# ADC2.net
KiCad netlist of a schematic drawn in EAGLE
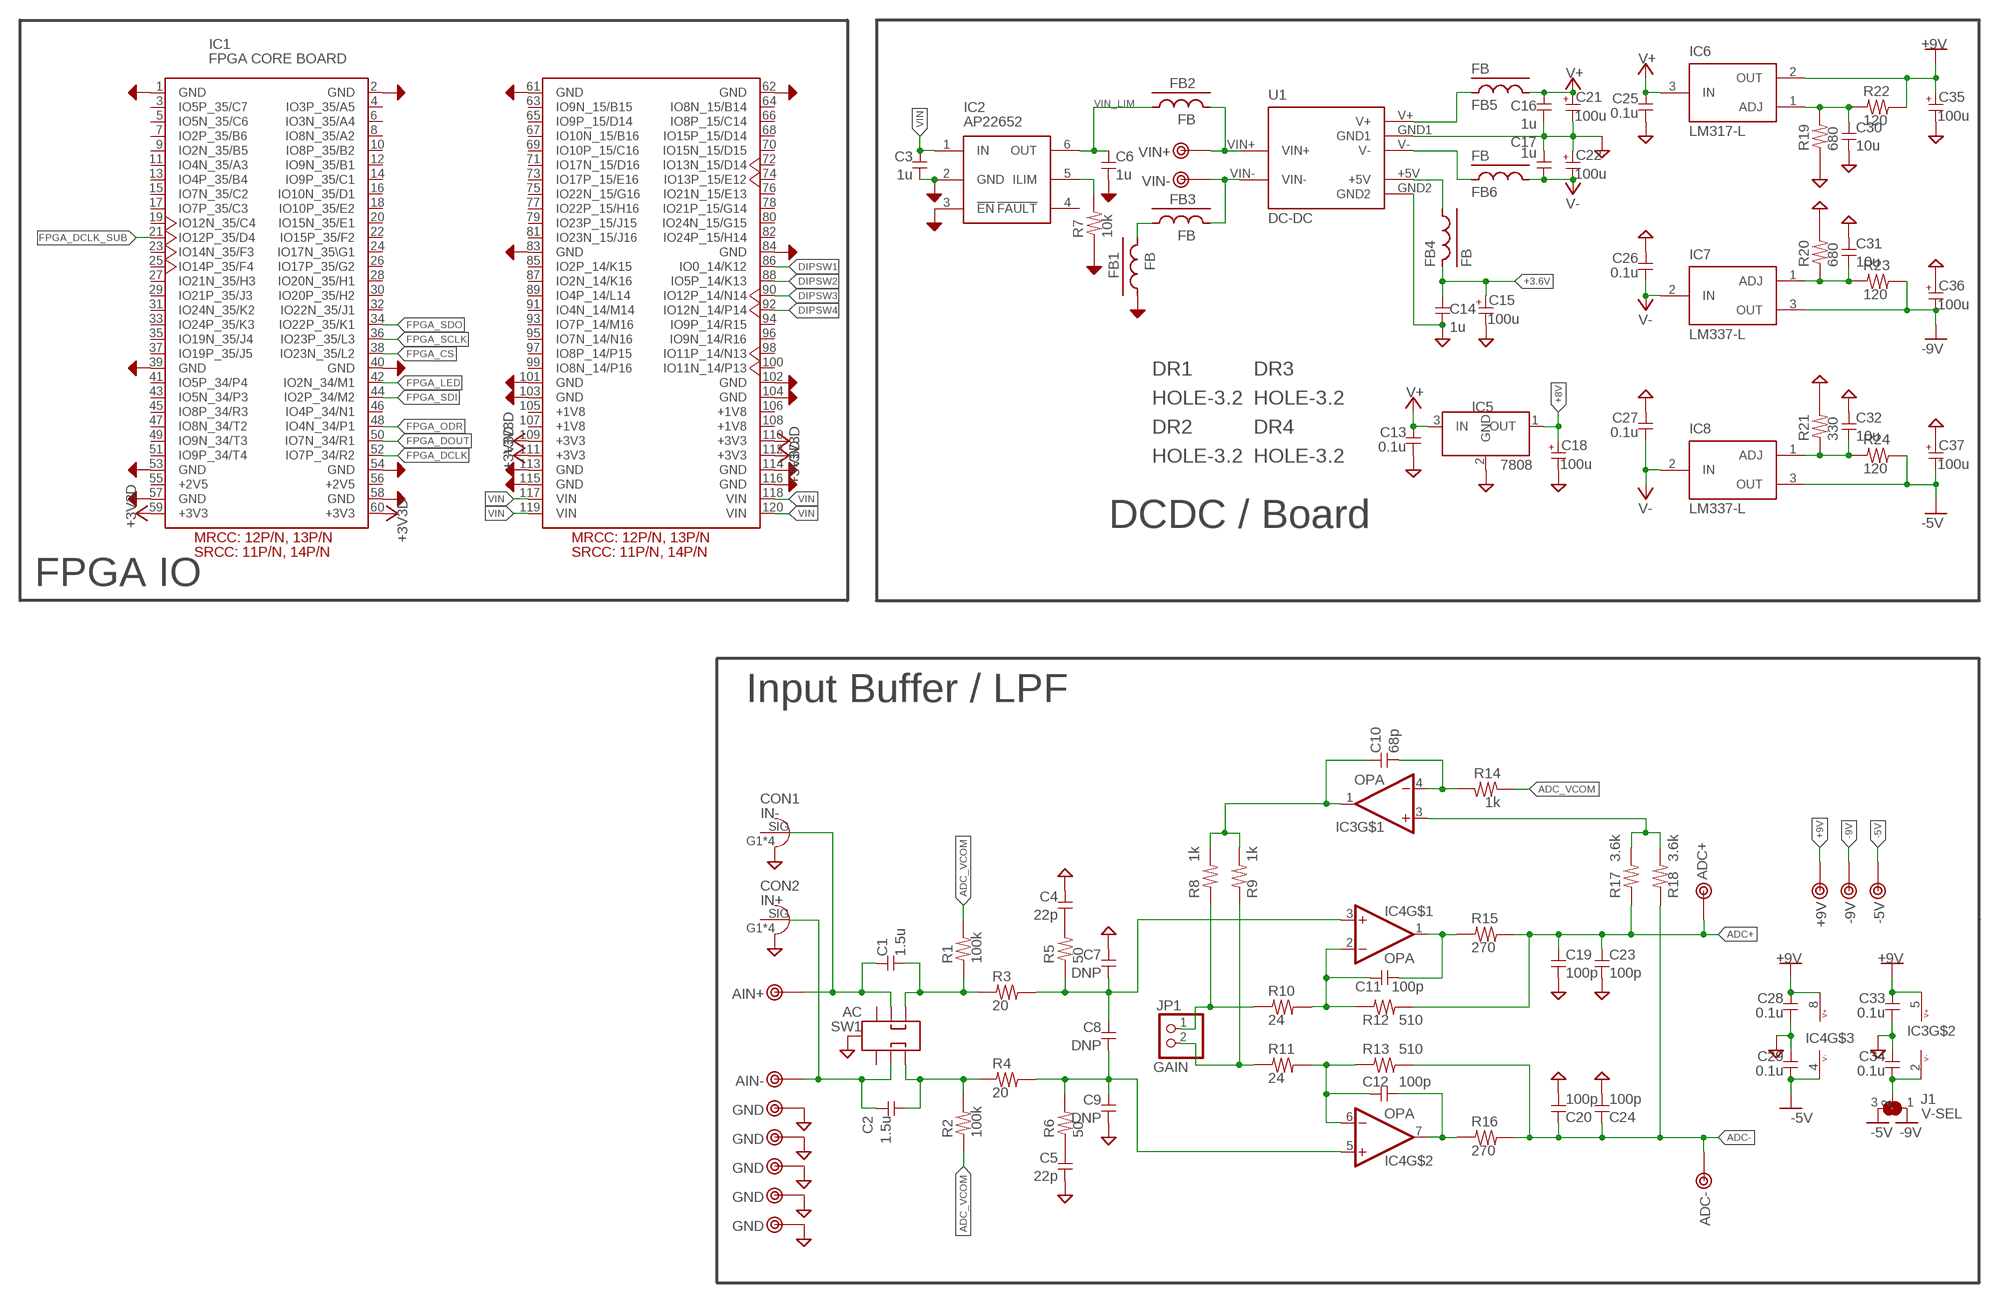
[diagram p0: schematic, sheet 1, part 1 of 2]
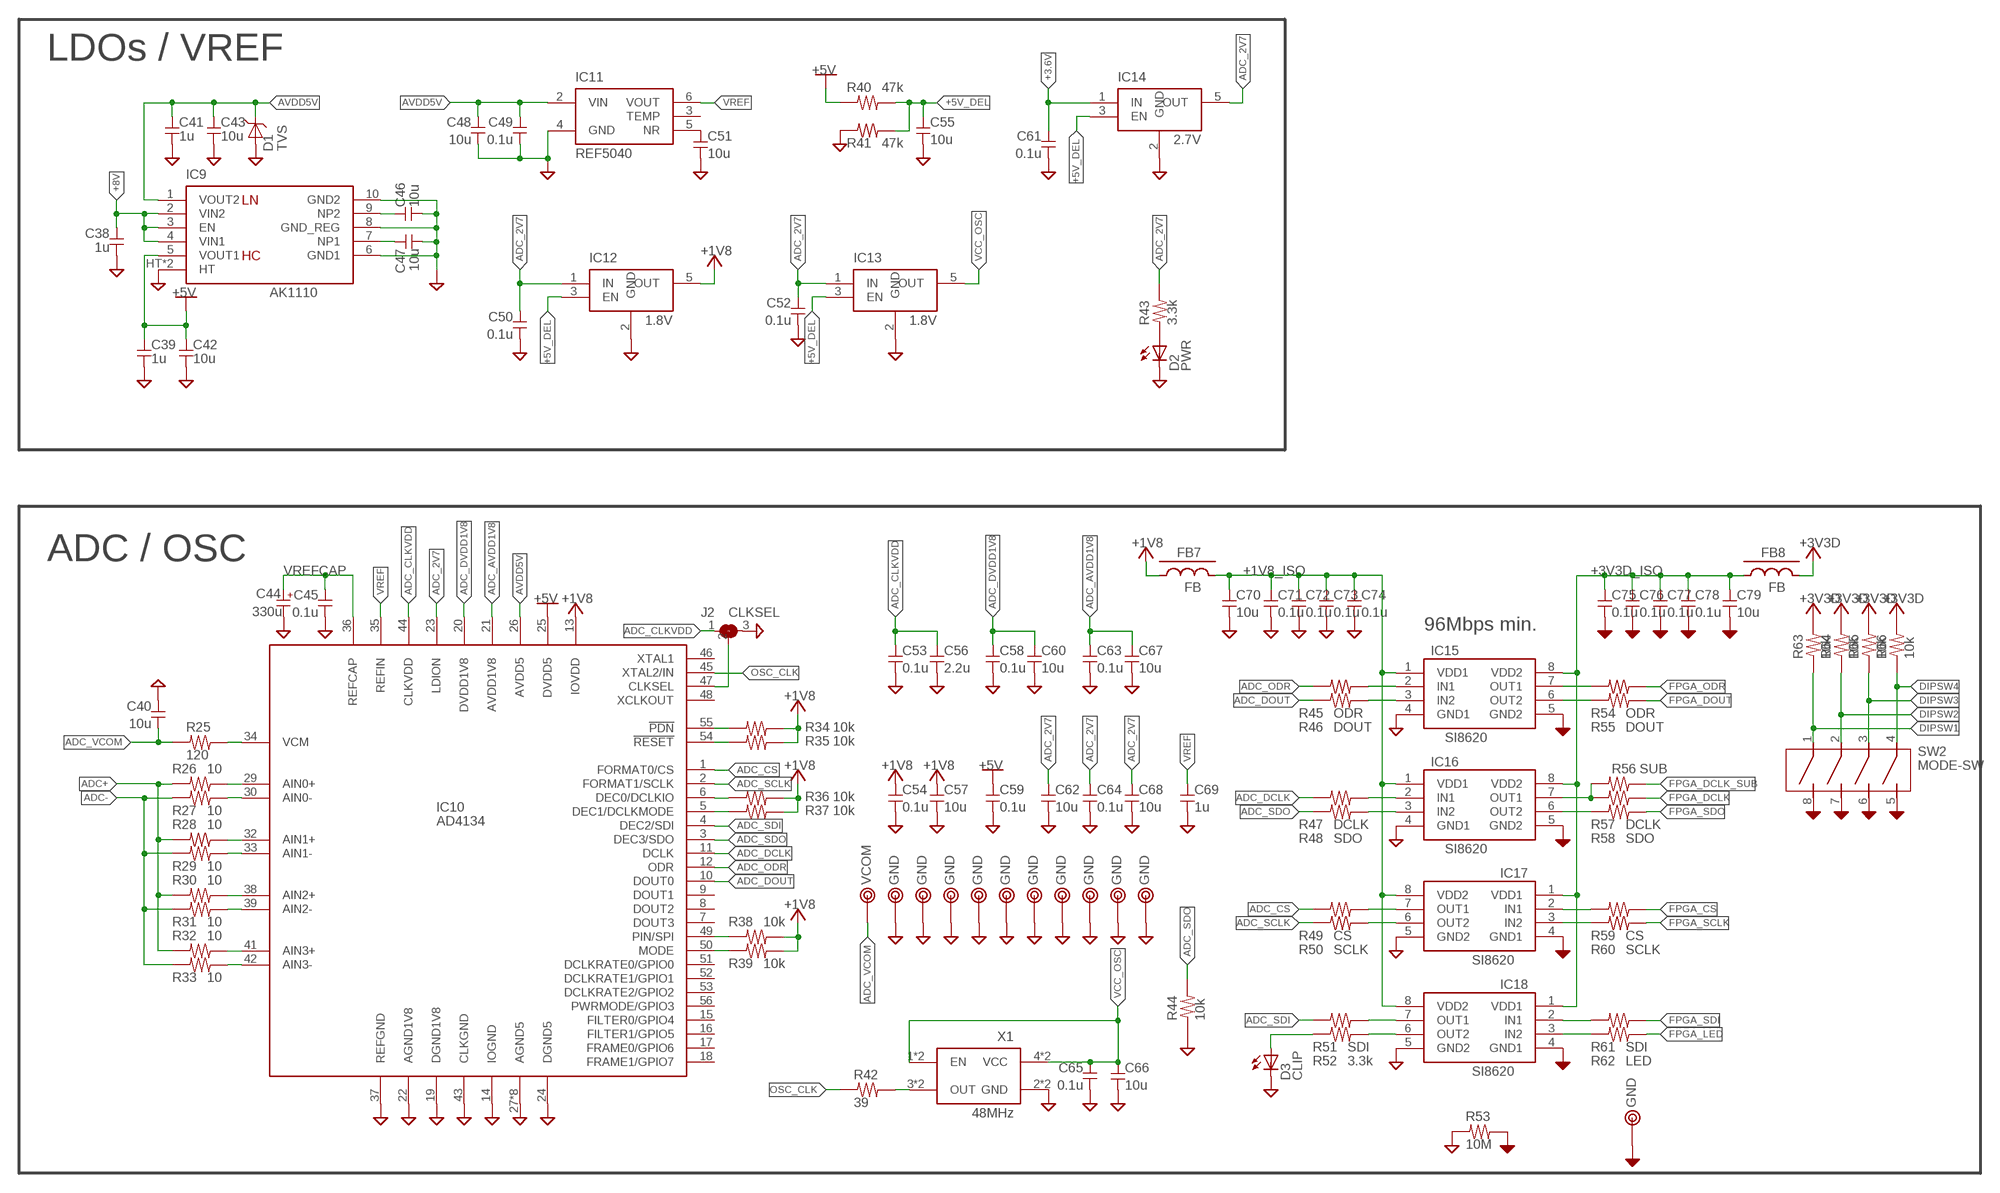
[diagram p1: schematic, sheet 1, part 2 of 2]

(export (version "E")
  (design (tool "Eeschema 10.0.6"))
  (components
    (comp (ref "C1")
      (value "1.5u")
      (footprint "eagle-import:C050")
      (libsource (lib "eagle-import") (part "C-5"))
    )
    (comp (ref "C2")
      (value "1.5u")
      (footprint "eagle-import:C050")
      (libsource (lib "eagle-import") (part "C-5"))
    )
    (comp (ref "C3")
      (value "1u")
      (footprint "eagle-import:1608C")
      (libsource (lib "eagle-import") (part "C-1608"))
    )
    (comp (ref "C4")
      (value "22p")
      (footprint "eagle-import:1608C")
      (libsource (lib "eagle-import") (part "C-1608"))
    )
    (comp (ref "C5")
      (value "22p")
      (footprint "eagle-import:1608C")
      (libsource (lib "eagle-import") (part "C-1608"))
    )
    (comp (ref "C6")
      (value "1u")
      (footprint "eagle-import:1608C")
      (libsource (lib "eagle-import") (part "C-1608"))
    )
    (comp (ref "C7")
      (value "DNP")
      (footprint "eagle-import:1608C")
      (libsource (lib "eagle-import") (part "C-1608"))
    )
    (comp (ref "C8")
      (value "DNP")
      (footprint "eagle-import:1608-3")
      (libsource (lib "eagle-import") (part "C-1608-3"))
    )
    (comp (ref "C9")
      (value "DNP")
      (footprint "eagle-import:1608C")
      (libsource (lib "eagle-import") (part "C-1608"))
    )
    (comp (ref "C10")
      (value "68p")
      (footprint "eagle-import:1608-3")
      (libsource (lib "eagle-import") (part "C-1608-3"))
    )
    (comp (ref "C11")
      (value "100p")
      (footprint "eagle-import:1608C")
      (libsource (lib "eagle-import") (part "C-1608"))
    )
    (comp (ref "C12")
      (value "100p")
      (footprint "eagle-import:1608C")
      (libsource (lib "eagle-import") (part "C-1608"))
    )
    (comp (ref "C13")
      (value "0.1u")
      (footprint "eagle-import:1608C")
      (libsource (lib "eagle-import") (part "C-1608"))
    )
    (comp (ref "C14")
      (value "1u")
      (footprint "eagle-import:1608C")
      (libsource (lib "eagle-import") (part "C-1608"))
    )
    (comp (ref "C15")
      (value "100u")
      (footprint "eagle-import:E2,5-8")
      (libsource (lib "eagle-import") (part "CPOLE2.5-8"))
    )
    (comp (ref "C16")
      (value "1u")
      (footprint "eagle-import:1608C")
      (libsource (lib "eagle-import") (part "C-1608"))
    )
    (comp (ref "C17")
      (value "1u")
      (footprint "eagle-import:1608C")
      (libsource (lib "eagle-import") (part "C-1608"))
    )
    (comp (ref "C18")
      (value "100u")
      (footprint "eagle-import:E2.5-6.5")
      (libsource (lib "eagle-import") (part "CPOLE2.5-6.5"))
    )
    (comp (ref "C19")
      (value "100p")
      (footprint "eagle-import:1608-3")
      (libsource (lib "eagle-import") (part "C-1608-3"))
    )
    (comp (ref "C20")
      (value "100p")
      (footprint "eagle-import:1608-3")
      (libsource (lib "eagle-import") (part "C-1608-3"))
    )
    (comp (ref "C21")
      (value "100u")
      (footprint "eagle-import:E2,5-8")
      (libsource (lib "eagle-import") (part "CPOLE2.5-8"))
    )
    (comp (ref "C22")
      (value "100u")
      (footprint "eagle-import:E2,5-8")
      (libsource (lib "eagle-import") (part "CPOLE2.5-8"))
    )
    (comp (ref "C23")
      (value "100p")
      (footprint "eagle-import:1608C")
      (libsource (lib "eagle-import") (part "C-1608"))
    )
    (comp (ref "C24")
      (value "100p")
      (footprint "eagle-import:1608C")
      (libsource (lib "eagle-import") (part "C-1608"))
    )
    (comp (ref "C25")
      (value "0.1u")
      (footprint "eagle-import:1608C")
      (libsource (lib "eagle-import") (part "C-1608"))
    )
    (comp (ref "C26")
      (value "0.1u")
      (footprint "eagle-import:1608C")
      (libsource (lib "eagle-import") (part "C-1608"))
    )
    (comp (ref "C27")
      (value "0.1u")
      (footprint "eagle-import:1608C")
      (libsource (lib "eagle-import") (part "C-1608"))
    )
    (comp (ref "C28")
      (value "0.1u")
      (footprint "eagle-import:1608C")
      (libsource (lib "eagle-import") (part "C-1608"))
    )
    (comp (ref "C29")
      (value "0.1u")
      (footprint "eagle-import:1608C")
      (libsource (lib "eagle-import") (part "C-1608"))
    )
    (comp (ref "C30")
      (value "10u")
      (footprint "eagle-import:3216")
      (libsource (lib "eagle-import") (part "C-3216"))
    )
    (comp (ref "C31")
      (value "10u")
      (footprint "eagle-import:3216")
      (libsource (lib "eagle-import") (part "C-3216"))
    )
    (comp (ref "C32")
      (value "10u")
      (footprint "eagle-import:3216")
      (libsource (lib "eagle-import") (part "C-3216"))
    )
    (comp (ref "C33")
      (value "0.1u")
      (footprint "eagle-import:1608C")
      (libsource (lib "eagle-import") (part "C-1608"))
    )
    (comp (ref "C34")
      (value "0.1u")
      (footprint "eagle-import:1608C")
      (libsource (lib "eagle-import") (part "C-1608"))
    )
    (comp (ref "C35")
      (value "100u")
      (footprint "eagle-import:E2.5-6.5")
      (libsource (lib "eagle-import") (part "CPOLE2.5-6.5"))
    )
    (comp (ref "C36")
      (value "100u")
      (footprint "eagle-import:E2.5-6.5")
      (libsource (lib "eagle-import") (part "CPOLE2.5-6.5"))
    )
    (comp (ref "C37")
      (value "100u")
      (footprint "eagle-import:E2.5-6.5")
      (libsource (lib "eagle-import") (part "CPOLE2.5-6.5"))
    )
    (comp (ref "C38")
      (value "1u")
      (footprint "eagle-import:1608C")
      (libsource (lib "eagle-import") (part "C-1608"))
    )
    (comp (ref "C39")
      (value "1u")
      (footprint "eagle-import:1608C")
      (libsource (lib "eagle-import") (part "C-1608"))
    )
    (comp (ref "C40")
      (value "10u")
      (footprint "eagle-import:2012")
      (libsource (lib "eagle-import") (part "C-2012"))
    )
    (comp (ref "C41")
      (value "1u")
      (footprint "eagle-import:1608C")
      (libsource (lib "eagle-import") (part "C-1608"))
    )
    (comp (ref "C42")
      (value "10u")
      (footprint "eagle-import:2012")
      (libsource (lib "eagle-import") (part "C-2012"))
    )
    (comp (ref "C43")
      (value "10u")
      (footprint "eagle-import:2012")
      (libsource (lib "eagle-import") (part "C-2012"))
    )
    (comp (ref "C44")
      (value "330u")
      (footprint "eagle-import:E2.5-6.5")
      (libsource (lib "eagle-import") (part "CPOLE2.5-6.5"))
    )
    (comp (ref "C45")
      (value "0.1u")
      (footprint "eagle-import:1608C")
      (libsource (lib "eagle-import") (part "C-1608"))
    )
    (comp (ref "C46")
      (value "10u")
      (footprint "eagle-import:2012")
      (libsource (lib "eagle-import") (part "C-2012"))
    )
    (comp (ref "C47")
      (value "10u")
      (footprint "eagle-import:2012")
      (libsource (lib "eagle-import") (part "C-2012"))
    )
    (comp (ref "C48")
      (value "10u")
      (footprint "eagle-import:2012")
      (libsource (lib "eagle-import") (part "C-2012"))
    )
    (comp (ref "C49")
      (value "0.1u")
      (footprint "eagle-import:1608C")
      (libsource (lib "eagle-import") (part "C-1608"))
    )
    (comp (ref "C50")
      (value "0.1u")
      (footprint "eagle-import:1608C")
      (libsource (lib "eagle-import") (part "C-1608"))
    )
    (comp (ref "C51")
      (value "10u")
      (footprint "eagle-import:3216")
      (libsource (lib "eagle-import") (part "C-3216"))
    )
    (comp (ref "C52")
      (value "0.1u")
      (footprint "eagle-import:1608C")
      (libsource (lib "eagle-import") (part "C-1608"))
    )
    (comp (ref "C53")
      (value "0.1u")
      (footprint "eagle-import:1608C")
      (libsource (lib "eagle-import") (part "C-1608"))
    )
    (comp (ref "C54")
      (value "0.1u")
      (footprint "eagle-import:1608C")
      (libsource (lib "eagle-import") (part "C-1608"))
    )
    (comp (ref "C55")
      (value "10u")
      (footprint "eagle-import:2012")
      (libsource (lib "eagle-import") (part "C-2012"))
    )
    (comp (ref "C56")
      (value "2.2u")
      (footprint "eagle-import:2012")
      (libsource (lib "eagle-import") (part "C-2012"))
    )
    (comp (ref "C57")
      (value "10u")
      (footprint "eagle-import:2012")
      (libsource (lib "eagle-import") (part "C-2012"))
    )
    (comp (ref "C58")
      (value "0.1u")
      (footprint "eagle-import:1608C")
      (libsource (lib "eagle-import") (part "C-1608"))
    )
    (comp (ref "C59")
      (value "0.1u")
      (footprint "eagle-import:1608C")
      (libsource (lib "eagle-import") (part "C-1608"))
    )
    (comp (ref "C60")
      (value "10u")
      (footprint "eagle-import:2012")
      (libsource (lib "eagle-import") (part "C-2012"))
    )
    (comp (ref "C61")
      (value "0.1u")
      (footprint "eagle-import:1608C")
      (libsource (lib "eagle-import") (part "C-1608"))
    )
    (comp (ref "C62")
      (value "10u")
      (footprint "eagle-import:2012")
      (libsource (lib "eagle-import") (part "C-2012"))
    )
    (comp (ref "C63")
      (value "0.1u")
      (footprint "eagle-import:1608C")
      (libsource (lib "eagle-import") (part "C-1608"))
    )
    (comp (ref "C64")
      (value "0.1u")
      (footprint "eagle-import:1608C")
      (libsource (lib "eagle-import") (part "C-1608"))
    )
    (comp (ref "C65")
      (value "0.1u")
      (footprint "eagle-import:1608C")
      (libsource (lib "eagle-import") (part "C-1608"))
    )
    (comp (ref "C66")
      (value "10u")
      (footprint "eagle-import:2012")
      (libsource (lib "eagle-import") (part "C-2012"))
    )
    (comp (ref "C67")
      (value "10u")
      (footprint "eagle-import:2012")
      (libsource (lib "eagle-import") (part "C-2012"))
    )
    (comp (ref "C68")
      (value "10u")
      (footprint "eagle-import:2012")
      (libsource (lib "eagle-import") (part "C-2012"))
    )
    (comp (ref "C69")
      (value "1u")
      (footprint "eagle-import:1608C")
      (libsource (lib "eagle-import") (part "C-1608"))
    )
    (comp (ref "C70")
      (value "10u")
      (footprint "eagle-import:1608C")
      (libsource (lib "eagle-import") (part "C-1608"))
    )
    (comp (ref "C71")
      (value "0.1u")
      (footprint "eagle-import:1608C")
      (libsource (lib "eagle-import") (part "C-1608"))
    )
    (comp (ref "C72")
      (value "0.1u")
      (footprint "eagle-import:1608C")
      (libsource (lib "eagle-import") (part "C-1608"))
    )
    (comp (ref "C73")
      (value "0.1u")
      (footprint "eagle-import:1608C")
      (libsource (lib "eagle-import") (part "C-1608"))
    )
    (comp (ref "C74")
      (value "0.1u")
      (footprint "eagle-import:1608C")
      (libsource (lib "eagle-import") (part "C-1608"))
    )
    (comp (ref "C75")
      (value "0.1u")
      (footprint "eagle-import:1608C")
      (libsource (lib "eagle-import") (part "C-1608"))
    )
    (comp (ref "C76")
      (value "0.1u")
      (footprint "eagle-import:1608C")
      (libsource (lib "eagle-import") (part "C-1608"))
    )
    (comp (ref "C77")
      (value "0.1u")
      (footprint "eagle-import:1608C")
      (libsource (lib "eagle-import") (part "C-1608"))
    )
    (comp (ref "C78")
      (value "0.1u")
      (footprint "eagle-import:1608C")
      (libsource (lib "eagle-import") (part "C-1608"))
    )
    (comp (ref "C79")
      (value "10u")
      (footprint "eagle-import:1608C")
      (libsource (lib "eagle-import") (part "C-1608"))
    )
    (comp (ref "CON1")
      (value "IN-")
      (footprint "eagle-import:SMA-EDGE")
      (libsource (lib "eagle-import") (part "SMA-142-0701-801"))
    )
    (comp (ref "CON2")
      (value "IN+")
      (footprint "eagle-import:SMA-EDGE")
      (libsource (lib "eagle-import") (part "SMA-142-0701-801"))
    )
    (comp (ref "D1")
      (value "TVS")
      (footprint "eagle-import:SOD323")
      (libsource (lib "eagle-import") (part "ZENER-SMD2"))
    )
    (comp (ref "D2")
      (value "PWR")
      (footprint "eagle-import:D1608")
      (libsource (lib "eagle-import") (part "LED-SMD1608"))
    )
    (comp (ref "D3")
      (value "CLIP")
      (footprint "eagle-import:D1608")
      (libsource (lib "eagle-import") (part "LED-SMD1608"))
    )
    (comp (ref "DR1")
      (value "HOLE-3.2")
      (footprint "eagle-import:HOLE_3.2")
      (libsource (lib "eagle-import") (part "HOLE-3.2"))
    )
    (comp (ref "DR2")
      (value "HOLE-3.2")
      (footprint "eagle-import:HOLE_3.2")
      (libsource (lib "eagle-import") (part "HOLE-3.2"))
    )
    (comp (ref "DR3")
      (value "HOLE-3.2")
      (footprint "eagle-import:HOLE_3.2")
      (libsource (lib "eagle-import") (part "HOLE-3.2"))
    )
    (comp (ref "DR4")
      (value "HOLE-3.2")
      (footprint "eagle-import:HOLE_3.2")
      (libsource (lib "eagle-import") (part "HOLE-3.2"))
    )
    (comp (ref "FB1")
      (value "FB")
      (footprint "eagle-import:2012-J")
      (libsource (lib "eagle-import") (part "FB-2012"))
    )
    (comp (ref "FB2")
      (value "FB")
      (footprint "eagle-import:2012-J")
      (libsource (lib "eagle-import") (part "FB-2012"))
    )
    (comp (ref "FB3")
      (value "FB")
      (footprint "eagle-import:2012-J")
      (libsource (lib "eagle-import") (part "FB-2012"))
    )
    (comp (ref "FB4")
      (value "FB")
      (footprint "eagle-import:2012-J")
      (libsource (lib "eagle-import") (part "FB-2012"))
    )
    (comp (ref "FB5")
      (value "FB")
      (footprint "eagle-import:2012-J")
      (libsource (lib "eagle-import") (part "FB-2012"))
    )
    (comp (ref "FB6")
      (value "FB")
      (footprint "eagle-import:2012-J")
      (libsource (lib "eagle-import") (part "FB-2012"))
    )
    (comp (ref "FB7")
      (value "FB")
      (footprint "eagle-import:1608-FB")
      (libsource (lib "eagle-import") (part "FB-1608FB"))
    )
    (comp (ref "FB8")
      (value "FB")
      (footprint "eagle-import:1608-FB")
      (libsource (lib "eagle-import") (part "FB-1608FB"))
    )
    (comp (ref "IC1")
      (value "FPGA CORE BOARD")
      (footprint "eagle-import:FPGA_CORE_BOARD")
      (libsource (lib "eagle-import") (part "FPGA_CORE_BOARD"))
    )
    (comp (ref "IC2")
      (value "AP22652")
      (footprint "eagle-import:SOT23-6")
      (libsource (lib "eagle-import") (part "AP22652"))
    )
    (comp (ref "IC3")
      (value "OPA")
      (footprint "eagle-import:SOT23-5")
      (libsource (lib "eagle-import") (part "OPA-1"))
    )
    (comp (ref "IC4")
      (value "OPA")
      (footprint "eagle-import:SOP8-3")
      (libsource (lib "eagle-import") (part "OPA-2-SOP"))
    )
    (comp (ref "IC5")
      (value "7808")
      (footprint "eagle-import:TO-92")
      (libsource (lib "eagle-import") (part "78LX"))
    )
    (comp (ref "IC6")
      (value "LM317-L")
      (footprint "eagle-import:TO-92")
      (libsource (lib "eagle-import") (part "LM317-L"))
    )
    (comp (ref "IC7")
      (value "LM337-L")
      (footprint "eagle-import:TO-92")
      (libsource (lib "eagle-import") (part "LM337-L"))
    )
    (comp (ref "IC8")
      (value "LM337-L")
      (footprint "eagle-import:TO-92")
      (libsource (lib "eagle-import") (part "LM337-L"))
    )
    (comp (ref "IC9")
      (value "AK1110")
      (footprint "eagle-import:PLP10")
      (libsource (lib "eagle-import") (part "AK1110"))
    )
    (comp (ref "IC10")
      (value "AD4134")
      (footprint "eagle-import:QFN56-HT-HOLE")
      (libsource (lib "eagle-import") (part "AD4134"))
    )
    (comp (ref "IC11")
      (value "REF5040")
      (footprint "eagle-import:SOP8")
      (libsource (lib "eagle-import") (part "REF5040"))
    )
    (comp (ref "IC12")
      (value "1.8V")
      (footprint "eagle-import:SOT23-5")
      (libsource (lib "eagle-import") (part "TLV740"))
    )
    (comp (ref "IC13")
      (value "1.8V")
      (footprint "eagle-import:SOT23-5")
      (libsource (lib "eagle-import") (part "TLV740"))
    )
    (comp (ref "IC14")
      (value "2.7V")
      (footprint "eagle-import:SOT23-5")
      (libsource (lib "eagle-import") (part "TLV740"))
    )
    (comp (ref "IC15")
      (value "SI8620")
      (footprint "eagle-import:SOP8-2")
      (libsource (lib "eagle-import") (part "SI8420"))
    )
    (comp (ref "IC16")
      (value "SI8620")
      (footprint "eagle-import:SOP8-2")
      (libsource (lib "eagle-import") (part "SI8420"))
    )
    (comp (ref "IC17")
      (value "SI8620")
      (footprint "eagle-import:SOP8-2")
      (libsource (lib "eagle-import") (part "SI8420"))
    )
    (comp (ref "IC18")
      (value "SI8620")
      (footprint "eagle-import:SOP8-2")
      (libsource (lib "eagle-import") (part "SI8420"))
    )
    (comp (ref "J1")
      (value "V-SEL")
      (footprint "eagle-import:1608-3-J")
      (libsource (lib "eagle-import") (part "SJ-3-1608"))
    )
    (comp (ref "J2")
      (value "CLKSEL")
      (footprint "eagle-import:1608-3-J")
      (libsource (lib "eagle-import") (part "SJ-3-1608"))
    )
    (comp (ref "JP1")
      (value "GAIN")
      (footprint "eagle-import:1X02")
      (libsource (lib "eagle-import") (part "PINHD-1X2"))
    )
    (comp (ref "R1")
      (value "100k")
      (footprint "eagle-import:1608-3")
      (libsource (lib "eagle-import") (part "R-1608-3"))
    )
    (comp (ref "R2")
      (value "100k")
      (footprint "eagle-import:1608-3")
      (libsource (lib "eagle-import") (part "R-1608-3"))
    )
    (comp (ref "R3")
      (value "20")
      (footprint "eagle-import:2012-R")
      (libsource (lib "eagle-import") (part "R-2012H"))
    )
    (comp (ref "R4")
      (value "20")
      (footprint "eagle-import:2012-R")
      (libsource (lib "eagle-import") (part "R-2012H"))
    )
    (comp (ref "R5")
      (value "50")
      (footprint "eagle-import:1608-3")
      (libsource (lib "eagle-import") (part "R-1608-3"))
    )
    (comp (ref "R6")
      (value "50")
      (footprint "eagle-import:1608-3")
      (libsource (lib "eagle-import") (part "R-1608-3"))
    )
    (comp (ref "R7")
      (value "10k")
      (footprint "eagle-import:1608")
      (libsource (lib "eagle-import") (part "R-1608"))
    )
    (comp (ref "R8")
      (value "1k")
      (footprint "eagle-import:1608-3")
      (libsource (lib "eagle-import") (part "R-1608-3"))
    )
    (comp (ref "R9")
      (value "1k")
      (footprint "eagle-import:1608-3")
      (libsource (lib "eagle-import") (part "R-1608-3"))
    )
    (comp (ref "R10")
      (value "24")
      (footprint "eagle-import:1608-3")
      (libsource (lib "eagle-import") (part "R-1608-3"))
    )
    (comp (ref "R11")
      (value "24")
      (footprint "eagle-import:1608-3")
      (libsource (lib "eagle-import") (part "R-1608-3"))
    )
    (comp (ref "R12")
      (value "510")
      (footprint "eagle-import:2012-R")
      (libsource (lib "eagle-import") (part "R-2012H"))
    )
    (comp (ref "R13")
      (value "510")
      (footprint "eagle-import:2012-R")
      (libsource (lib "eagle-import") (part "R-2012H"))
    )
    (comp (ref "R14")
      (value "1k")
      (footprint "eagle-import:1608")
      (libsource (lib "eagle-import") (part "R-1608"))
    )
    (comp (ref "R15")
      (value "270")
      (footprint "eagle-import:2012-R")
      (libsource (lib "eagle-import") (part "R-2012H"))
    )
    (comp (ref "R16")
      (value "270")
      (footprint "eagle-import:2012-R")
      (libsource (lib "eagle-import") (part "R-2012H"))
    )
    (comp (ref "R17")
      (value "3.6k")
      (footprint "eagle-import:1608")
      (libsource (lib "eagle-import") (part "R-1608"))
    )
    (comp (ref "R18")
      (value "3.6k")
      (footprint "eagle-import:1608")
      (libsource (lib "eagle-import") (part "R-1608"))
    )
    (comp (ref "R19")
      (value "680")
      (footprint "eagle-import:1608")
      (libsource (lib "eagle-import") (part "R-1608"))
    )
    (comp (ref "R20")
      (value "680")
      (footprint "eagle-import:1608")
      (libsource (lib "eagle-import") (part "R-1608"))
    )
    (comp (ref "R21")
      (value "330")
      (footprint "eagle-import:1608")
      (libsource (lib "eagle-import") (part "R-1608"))
    )
    (comp (ref "R22")
      (value "120")
      (footprint "eagle-import:1608")
      (libsource (lib "eagle-import") (part "R-1608"))
    )
    (comp (ref "R23")
      (value "120")
      (footprint "eagle-import:1608")
      (libsource (lib "eagle-import") (part "R-1608"))
    )
    (comp (ref "R24")
      (value "120")
      (footprint "eagle-import:1608")
      (libsource (lib "eagle-import") (part "R-1608"))
    )
    (comp (ref "R25")
      (value "120")
      (footprint "eagle-import:1608")
      (libsource (lib "eagle-import") (part "R-1608"))
    )
    (comp (ref "R26")
      (value "10")
      (footprint "eagle-import:1608-3")
      (libsource (lib "eagle-import") (part "R-1608-3"))
    )
    (comp (ref "R27")
      (value "10")
      (footprint "eagle-import:1608")
      (libsource (lib "eagle-import") (part "R-1608"))
    )
    (comp (ref "R28")
      (value "10")
      (footprint "eagle-import:1608-3")
      (libsource (lib "eagle-import") (part "R-1608-3"))
    )
    (comp (ref "R29")
      (value "10")
      (footprint "eagle-import:1608-3")
      (libsource (lib "eagle-import") (part "R-1608-3"))
    )
    (comp (ref "R30")
      (value "10")
      (footprint "eagle-import:1608-3")
      (libsource (lib "eagle-import") (part "R-1608-3"))
    )
    (comp (ref "R31")
      (value "10")
      (footprint "eagle-import:1608-3")
      (libsource (lib "eagle-import") (part "R-1608-3"))
    )
    (comp (ref "R32")
      (value "10")
      (footprint "eagle-import:1608")
      (libsource (lib "eagle-import") (part "R-1608"))
    )
    (comp (ref "R33")
      (value "10")
      (footprint "eagle-import:1608-3")
      (libsource (lib "eagle-import") (part "R-1608-3"))
    )
    (comp (ref "R34")
      (value "10k")
      (footprint "eagle-import:1608")
      (libsource (lib "eagle-import") (part "R-1608"))
    )
    (comp (ref "R35")
      (value "10k")
      (footprint "eagle-import:1608")
      (libsource (lib "eagle-import") (part "R-1608"))
    )
    (comp (ref "R36")
      (value "10k")
      (footprint "eagle-import:1608")
      (libsource (lib "eagle-import") (part "R-1608"))
    )
    (comp (ref "R37")
      (value "10k")
      (footprint "eagle-import:1608")
      (libsource (lib "eagle-import") (part "R-1608"))
    )
    (comp (ref "R38")
      (value "10k")
      (footprint "eagle-import:1608")
      (libsource (lib "eagle-import") (part "R-1608"))
    )
    (comp (ref "R39")
      (value "10k")
      (footprint "eagle-import:1608")
      (libsource (lib "eagle-import") (part "R-1608"))
    )
    (comp (ref "R40")
      (value "47k")
      (footprint "eagle-import:1608")
      (libsource (lib "eagle-import") (part "R-1608"))
    )
    (comp (ref "R41")
      (value "47k")
      (footprint "eagle-import:1608")
      (libsource (lib "eagle-import") (part "R-1608"))
    )
    (comp (ref "R42")
      (value "39")
      (footprint "eagle-import:1608")
      (libsource (lib "eagle-import") (part "R-1608"))
    )
    (comp (ref "R43")
      (value "3.3k")
      (footprint "eagle-import:1608")
      (libsource (lib "eagle-import") (part "R-1608"))
    )
    (comp (ref "R44")
      (value "10k")
      (footprint "eagle-import:1608")
      (libsource (lib "eagle-import") (part "R-1608"))
    )
    (comp (ref "R45")
      (value "ODR")
      (footprint "eagle-import:1608-3")
      (libsource (lib "eagle-import") (part "R-1608-3"))
    )
    (comp (ref "R46")
      (value "DOUT")
      (footprint "eagle-import:1608-3")
      (libsource (lib "eagle-import") (part "R-1608-3"))
    )
    (comp (ref "R47")
      (value "DCLK")
      (footprint "eagle-import:1608")
      (libsource (lib "eagle-import") (part "R-1608"))
    )
    (comp (ref "R48")
      (value "SDO")
      (footprint "eagle-import:1608")
      (libsource (lib "eagle-import") (part "R-1608"))
    )
    (comp (ref "R49")
      (value "CS")
      (footprint "eagle-import:1608")
      (libsource (lib "eagle-import") (part "R-1608"))
    )
    (comp (ref "R50")
      (value "SCLK")
      (footprint "eagle-import:1608")
      (libsource (lib "eagle-import") (part "R-1608"))
    )
    (comp (ref "R51")
      (value "SDI")
      (footprint "eagle-import:1608")
      (libsource (lib "eagle-import") (part "R-1608"))
    )
    (comp (ref "R52")
      (value "3.3k")
      (footprint "eagle-import:1608")
      (libsource (lib "eagle-import") (part "R-1608"))
    )
    (comp (ref "R53")
      (value "10M")
      (footprint "eagle-import:0204_7")
      (libsource (lib "eagle-import") (part "R-7.5"))
    )
    (comp (ref "R54")
      (value "ODR")
      (footprint "eagle-import:1608")
      (libsource (lib "eagle-import") (part "R-1608"))
    )
    (comp (ref "R55")
      (value "DOUT")
      (footprint "eagle-import:1608")
      (libsource (lib "eagle-import") (part "R-1608"))
    )
    (comp (ref "R56")
      (value "SUB")
      (footprint "eagle-import:1608")
      (libsource (lib "eagle-import") (part "R-1608"))
    )
    (comp (ref "R57")
      (value "DCLK")
      (footprint "eagle-import:1608")
      (libsource (lib "eagle-import") (part "R-1608"))
    )
    (comp (ref "R58")
      (value "SDO")
      (footprint "eagle-import:1608")
      (libsource (lib "eagle-import") (part "R-1608"))
    )
    (comp (ref "R59")
      (value "CS")
      (footprint "eagle-import:1608")
      (libsource (lib "eagle-import") (part "R-1608"))
    )
    (comp (ref "R60")
      (value "SCLK")
      (footprint "eagle-import:1608")
      (libsource (lib "eagle-import") (part "R-1608"))
    )
    (comp (ref "R61")
      (value "SDI")
      (footprint "eagle-import:1608")
      (libsource (lib "eagle-import") (part "R-1608"))
    )
    (comp (ref "R62")
      (value "LED")
      (footprint "eagle-import:1608")
      (libsource (lib "eagle-import") (part "R-1608"))
    )
    (comp (ref "R63")
      (value "10k")
      (footprint "eagle-import:1608")
      (libsource (lib "eagle-import") (part "R-1608"))
    )
    (comp (ref "R64")
      (value "10k")
      (footprint "eagle-import:1608")
      (libsource (lib "eagle-import") (part "R-1608"))
    )
    (comp (ref "R65")
      (value "10k")
      (footprint "eagle-import:1608")
      (libsource (lib "eagle-import") (part "R-1608"))
    )
    (comp (ref "R66")
      (value "10k")
      (footprint "eagle-import:1608")
      (libsource (lib "eagle-import") (part "R-1608"))
    )
    (comp (ref "SW1")
      (value "AC")
      (footprint "eagle-import:SS22E01G5")
      (libsource (lib "eagle-import") (part "SS22E01G5"))
    )
    (comp (ref "SW2")
      (value "MODE-SW")
      (footprint "eagle-import:DIPSW-4")
      (libsource (lib "eagle-import") (part "DIPSW-4"))
    )
    (comp (ref "TP1")
      (value "GND")
      (footprint "eagle-import:TESTPIN-MID")
      (libsource (lib "eagle-import") (part "TESTPIN-MID"))
    )
    (comp (ref "TP2")
      (value "AIN+")
      (footprint "eagle-import:TESTPIN-MID")
      (libsource (lib "eagle-import") (part "TESTPIN-MID"))
    )
    (comp (ref "TP3")
      (value "GND")
      (footprint "eagle-import:TESTPIN-MID")
      (libsource (lib "eagle-import") (part "TESTPIN-MID"))
    )
    (comp (ref "TP4")
      (value "GND")
      (footprint "eagle-import:TESTPIN")
      (libsource (lib "eagle-import") (part "TESTPIN"))
    )
    (comp (ref "TP5")
      (value "GND")
      (footprint "eagle-import:TESTPIN")
      (libsource (lib "eagle-import") (part "TESTPIN"))
    )
    (comp (ref "TP6")
      (value "AIN-")
      (footprint "eagle-import:TESTPIN-MID")
      (libsource (lib "eagle-import") (part "TESTPIN-MID"))
    )
    (comp (ref "TP7")
      (value "GND")
      (footprint "eagle-import:TESTPIN")
      (libsource (lib "eagle-import") (part "TESTPIN"))
    )
    (comp (ref "TP8")
      (value "GND")
      (footprint "eagle-import:TESTPIN")
      (libsource (lib "eagle-import") (part "TESTPIN"))
    )
    (comp (ref "TP9")
      (value "GND")
      (footprint "eagle-import:TESTPIN")
      (libsource (lib "eagle-import") (part "TESTPIN"))
    )
    (comp (ref "TP10")
      (value "GND")
      (footprint "eagle-import:TESTPIN")
      (libsource (lib "eagle-import") (part "TESTPIN"))
    )
    (comp (ref "TP11")
      (value "GND")
      (footprint "eagle-import:TESTPIN")
      (libsource (lib "eagle-import") (part "TESTPIN"))
    )
    (comp (ref "TP12")
      (value "GND")
      (footprint "eagle-import:TESTPIN")
      (libsource (lib "eagle-import") (part "TESTPIN"))
    )
    (comp (ref "TP13")
      (value "GND")
      (footprint "eagle-import:TESTPIN")
      (libsource (lib "eagle-import") (part "TESTPIN"))
    )
    (comp (ref "TP14")
      (value "GND")
      (footprint "eagle-import:TESTPIN")
      (libsource (lib "eagle-import") (part "TESTPIN"))
    )
    (comp (ref "TP15")
      (value "GND")
      (footprint "eagle-import:TESTPIN")
      (libsource (lib "eagle-import") (part "TESTPIN"))
    )
    (comp (ref "TP16")
      (value "+9V")
      (footprint "eagle-import:TESTPIN")
      (libsource (lib "eagle-import") (part "TESTPIN"))
    )
    (comp (ref "TP17")
      (value "-9V")
      (footprint "eagle-import:TESTPIN")
      (libsource (lib "eagle-import") (part "TESTPIN"))
    )
    (comp (ref "TP18")
      (value "-5V")
      (footprint "eagle-import:TESTPIN")
      (libsource (lib "eagle-import") (part "TESTPIN"))
    )
    (comp (ref "TP19")
      (value "GND")
      (footprint "eagle-import:TESTPIN-MID")
      (libsource (lib "eagle-import") (part "TESTPIN-MID"))
    )
    (comp (ref "TP20")
      (value "GND")
      (footprint "eagle-import:TESTPIN-MID")
      (libsource (lib "eagle-import") (part "TESTPIN-MID"))
    )
    (comp (ref "TP21")
      (value "GND")
      (footprint "eagle-import:TESTPIN-MID")
      (libsource (lib "eagle-import") (part "TESTPIN-MID"))
    )
    (comp (ref "TP22")
      (value "VCOM")
      (footprint "eagle-import:TESTPIN")
      (libsource (lib "eagle-import") (part "TESTPIN"))
    )
    (comp (ref "TP23")
      (value "ADC+")
      (footprint "eagle-import:TESTPIN")
      (libsource (lib "eagle-import") (part "TESTPIN"))
    )
    (comp (ref "TP24")
      (value "ADC-")
      (footprint "eagle-import:TESTPIN")
      (libsource (lib "eagle-import") (part "TESTPIN"))
    )
    (comp (ref "TP30")
      (value "VIN+")
      (footprint "eagle-import:TESTPIN")
      (libsource (lib "eagle-import") (part "TESTPIN"))
    )
    (comp (ref "TP31")
      (value "VIN-")
      (footprint "eagle-import:TESTPIN")
      (libsource (lib "eagle-import") (part "TESTPIN"))
    )
    (comp (ref "U1")
      (value "DC-DC")
      (footprint "eagle-import:DCDC")
      (libsource (lib "eagle-import") (part "DC-DC"))
    )
    (comp (ref "X1")
      (value "48MHz")
      (footprint "eagle-import:KC7050")
      (libsource (lib "eagle-import") (part "OSC-KC7050"))
    )
  )
  (nets
    (net (code "1") (name "+1V8") (class "Default")
      (node (ref "C54") (pin "1") (pinfunction "1_1") (pintype "passive"))
      (node (ref "C57") (pin "1") (pinfunction "1_1") (pintype "passive"))
      (node (ref "FB7") (pin "1") (pinfunction "1_1") (pintype "passive"))
      (node (ref "IC10") (pin "13") (pinfunction "IOVDD_13") (pintype "input"))
      (node (ref "IC12") (pin "5") (pinfunction "OUT_5") (pintype "output"))
      (node (ref "R34") (pin "2") (pinfunction "2_2") (pintype "passive"))
      (node (ref "R35") (pin "2") (pinfunction "2_2") (pintype "passive"))
      (node (ref "R36") (pin "2") (pinfunction "2_2") (pintype "passive"))
      (node (ref "R37") (pin "2") (pinfunction "2_2") (pintype "passive"))
      (node (ref "R38") (pin "2") (pinfunction "2_2") (pintype "passive"))
      (node (ref "R39") (pin "2") (pinfunction "2_2") (pintype "passive"))
    )
    (net (code "2") (name "+3.6V") (class "Default")
      (node (ref "C14") (pin "1") (pinfunction "1_1") (pintype "passive"))
      (node (ref "C15") (pin "+") (pinfunction "1_+") (pintype "passive"))
      (node (ref "C61") (pin "1") (pinfunction "1_1") (pintype "passive"))
      (node (ref "FB4") (pin "1") (pinfunction "1_1") (pintype "passive"))
      (node (ref "IC14") (pin "1") (pinfunction "IN_1") (pintype "input"))
    )
    (net (code "3") (name "+3V3D") (class "Default")
      (node (ref "FB8") (pin "2") (pinfunction "2_2") (pintype "passive"))
      (node (ref "IC1") (pin "109") (pinfunction "+3V3_109") (pintype "bidirectional"))
      (node (ref "IC1") (pin "110") (pinfunction "+3V3_110") (pintype "bidirectional"))
      (node (ref "IC1") (pin "111") (pinfunction "+3V3_111") (pintype "bidirectional"))
      (node (ref "IC1") (pin "112") (pinfunction "+3V3_112") (pintype "bidirectional"))
      (node (ref "IC1") (pin "59") (pinfunction "+3V3_59") (pintype "bidirectional"))
      (node (ref "IC1") (pin "60") (pinfunction "+3V3_60") (pintype "bidirectional"))
      (node (ref "R63") (pin "2") (pinfunction "2_2") (pintype "passive"))
      (node (ref "R64") (pin "2") (pinfunction "2_2") (pintype "passive"))
      (node (ref "R65") (pin "2") (pinfunction "2_2") (pintype "passive"))
      (node (ref "R66") (pin "2") (pinfunction "2_2") (pintype "passive"))
    )
    (net (code "4") (name "+5V") (class "Default")
      (node (ref "C39") (pin "1") (pinfunction "1_1") (pintype "passive"))
      (node (ref "C42") (pin "1") (pinfunction "1_1") (pintype "passive"))
      (node (ref "C59") (pin "1") (pinfunction "1_1") (pintype "passive"))
      (node (ref "IC10") (pin "25") (pinfunction "DVDD5_25") (pintype "input"))
      (node (ref "IC9") (pin "5") (pinfunction "VOUT1_5") (pintype "output"))
      (node (ref "R40") (pin "1") (pinfunction "1_1") (pintype "passive"))
    )
    (net (code "5") (name "+5V_DEL") (class "Default")
      (node (ref "C55") (pin "1") (pinfunction "1_1") (pintype "passive"))
      (node (ref "IC12") (pin "3") (pinfunction "EN_3") (pintype "input"))
      (node (ref "IC13") (pin "3") (pinfunction "EN_3") (pintype "input"))
      (node (ref "IC14") (pin "3") (pinfunction "EN_3") (pintype "input"))
      (node (ref "R40") (pin "2") (pinfunction "2_2") (pintype "passive"))
      (node (ref "R41") (pin "2") (pinfunction "2_2") (pintype "passive"))
    )
    (net (code "6") (name "+8V") (class "Default")
      (node (ref "C18") (pin "+") (pinfunction "1_+") (pintype "passive"))
      (node (ref "C38") (pin "1") (pinfunction "1_1") (pintype "passive"))
      (node (ref "IC5") (pin "1") (pinfunction "OUT_1") (pintype "output"))
      (node (ref "IC9") (pin "2") (pinfunction "VIN2_2") (pintype "input"))
      (node (ref "IC9") (pin "3") (pinfunction "EN_3") (pintype "input"))
      (node (ref "IC9") (pin "4") (pinfunction "VIN1_4") (pintype "input"))
    )
    (net (code "7") (name "+9V") (class "Default")
      (node (ref "C28") (pin "1") (pinfunction "1_1") (pintype "passive"))
      (node (ref "C33") (pin "1") (pinfunction "1_1") (pintype "passive"))
      (node (ref "C35") (pin "+") (pinfunction "1_+") (pintype "passive"))
      (node (ref "IC3") (pin "5") (pinfunction "V+_5") (pintype "input"))
      (node (ref "IC4") (pin "8") (pinfunction "V+_8") (pintype "input"))
      (node (ref "IC6") (pin "2") (pinfunction "OUT_2") (pintype "output"))
      (node (ref "R22") (pin "2") (pinfunction "2_2") (pintype "passive"))
      (node (ref "TP16") (pin "1") (pinfunction "1_1") (pintype "passive"))
    )
    (net (code "8") (name "-5V") (class "Default")
      (node (ref "C29") (pin "2") (pinfunction "2_2") (pintype "passive"))
      (node (ref "C37") (pin "-") (pinfunction "2_-") (pintype "passive"))
      (node (ref "IC4") (pin "4") (pinfunction "V-_4") (pintype "input"))
      (node (ref "IC8") (pin "3") (pinfunction "OUT_3") (pintype "output"))
      (node (ref "J1") (pin "3") (pinfunction "3_3") (pintype "passive"))
      (node (ref "R24") (pin "2") (pinfunction "2_2") (pintype "passive"))
      (node (ref "TP18") (pin "1") (pinfunction "1_1") (pintype "passive"))
    )
    (net (code "9") (name "-9V") (class "Default")
      (node (ref "C36") (pin "-") (pinfunction "2_-") (pintype "passive"))
      (node (ref "IC7") (pin "3") (pinfunction "OUT_3") (pintype "output"))
      (node (ref "J1") (pin "1") (pinfunction "1_1") (pintype "passive"))
      (node (ref "R23") (pin "2") (pinfunction "2_2") (pintype "passive"))
      (node (ref "TP17") (pin "1") (pinfunction "1_1") (pintype "passive"))
    )
    (net (code "10") (name "/+1V8_ISO") (class "Default")
      (node (ref "C70") (pin "1") (pinfunction "1_1") (pintype "passive"))
      (node (ref "C71") (pin "1") (pinfunction "1_1") (pintype "passive"))
      (node (ref "C72") (pin "1") (pinfunction "1_1") (pintype "passive"))
      (node (ref "C73") (pin "1") (pinfunction "1_1") (pintype "passive"))
      (node (ref "C74") (pin "1") (pinfunction "1_1") (pintype "passive"))
      (node (ref "FB7") (pin "2") (pinfunction "2_2") (pintype "passive"))
      (node (ref "IC15") (pin "1") (pinfunction "VDD1_1") (pintype "power_in"))
      (node (ref "IC16") (pin "1") (pinfunction "VDD1_1") (pintype "power_in"))
      (node (ref "IC17") (pin "8") (pinfunction "VDD2_8") (pintype "power_in"))
      (node (ref "IC18") (pin "8") (pinfunction "VDD2_8") (pintype "power_in"))
    )
    (net (code "11") (name "/+3V3D_ISO") (class "Default")
      (node (ref "C75") (pin "1") (pinfunction "1_1") (pintype "passive"))
      (node (ref "C76") (pin "1") (pinfunction "1_1") (pintype "passive"))
      (node (ref "C77") (pin "1") (pinfunction "1_1") (pintype "passive"))
      (node (ref "C78") (pin "1") (pinfunction "1_1") (pintype "passive"))
      (node (ref "C79") (pin "1") (pinfunction "1_1") (pintype "passive"))
      (node (ref "FB8") (pin "1") (pinfunction "1_1") (pintype "passive"))
      (node (ref "IC15") (pin "8") (pinfunction "VDD2_8") (pintype "power_in"))
      (node (ref "IC16") (pin "8") (pinfunction "VDD2_8") (pintype "power_in"))
      (node (ref "IC17") (pin "1") (pinfunction "VDD1_1") (pintype "power_in"))
      (node (ref "IC18") (pin "1") (pinfunction "VDD1_1") (pintype "power_in"))
    )
    (net (code "12") (name "/VIN_LIM") (class "Default")
      (node (ref "C6") (pin "1") (pinfunction "1_1") (pintype "passive"))
      (node (ref "FB2") (pin "1") (pinfunction "1_1") (pintype "passive"))
      (node (ref "IC2") (pin "6") (pinfunction "OUT_6") (pintype "output"))
    )
    (net (code "13") (name "/VREFCAP") (class "Default")
      (node (ref "C44") (pin "+") (pinfunction "1_+") (pintype "passive"))
      (node (ref "C45") (pin "1") (pinfunction "1_1") (pintype "passive"))
      (node (ref "IC10") (pin "36") (pinfunction "REFCAP_36") (pintype "input"))
    )
    (net (code "14") (name "ADC+") (class "Default")
      (node (ref "C19") (pin "1") (pinfunction "1_1") (pintype "passive"))
      (node (ref "C23") (pin "1") (pinfunction "1_1") (pintype "passive"))
      (node (ref "R12") (pin "2") (pinfunction "2_2") (pintype "passive"))
      (node (ref "R15") (pin "2") (pinfunction "2_2") (pintype "passive"))
      (node (ref "R17") (pin "1") (pinfunction "1_1") (pintype "passive"))
      (node (ref "R26") (pin "1") (pinfunction "1_1") (pintype "passive"))
      (node (ref "R28") (pin "1") (pinfunction "1_1") (pintype "passive"))
      (node (ref "R30") (pin "1") (pinfunction "1_1") (pintype "passive"))
      (node (ref "R32") (pin "1") (pinfunction "1_1") (pintype "passive"))
      (node (ref "TP23") (pin "1") (pinfunction "1_1") (pintype "passive"))
    )
    (net (code "15") (name "ADC-") (class "Default")
      (node (ref "C20") (pin "1") (pinfunction "1_1") (pintype "passive"))
      (node (ref "C24") (pin "1") (pinfunction "1_1") (pintype "passive"))
      (node (ref "R13") (pin "2") (pinfunction "2_2") (pintype "passive"))
      (node (ref "R16") (pin "2") (pinfunction "2_2") (pintype "passive"))
      (node (ref "R18") (pin "1") (pinfunction "1_1") (pintype "passive"))
      (node (ref "R27") (pin "1") (pinfunction "1_1") (pintype "passive"))
      (node (ref "R29") (pin "1") (pinfunction "1_1") (pintype "passive"))
      (node (ref "R31") (pin "1") (pinfunction "1_1") (pintype "passive"))
      (node (ref "R33") (pin "1") (pinfunction "1_1") (pintype "passive"))
      (node (ref "TP24") (pin "1") (pinfunction "1_1") (pintype "passive"))
    )
    (net (code "16") (name "ADC_2V7") (class "Default")
      (node (ref "C50") (pin "1") (pinfunction "1_1") (pintype "passive"))
      (node (ref "C52") (pin "1") (pinfunction "1_1") (pintype "passive"))
      (node (ref "C62") (pin "1") (pinfunction "1_1") (pintype "passive"))
      (node (ref "C64") (pin "1") (pinfunction "1_1") (pintype "passive"))
      (node (ref "C68") (pin "1") (pinfunction "1_1") (pintype "passive"))
      (node (ref "IC10") (pin "23") (pinfunction "LDION_23") (pintype "input"))
      (node (ref "IC12") (pin "1") (pinfunction "IN_1") (pintype "input"))
      (node (ref "IC13") (pin "1") (pinfunction "IN_1") (pintype "input"))
      (node (ref "IC14") (pin "5") (pinfunction "OUT_5") (pintype "output"))
      (node (ref "R43") (pin "2") (pinfunction "2_2") (pintype "passive"))
    )
    (net (code "17") (name "ADC_AVDD1V8") (class "Default")
      (node (ref "C63") (pin "1") (pinfunction "1_1") (pintype "passive"))
      (node (ref "C67") (pin "1") (pinfunction "1_1") (pintype "passive"))
      (node (ref "IC10") (pin "21") (pinfunction "AVDD1V8_21") (pintype "input"))
    )
    (net (code "18") (name "ADC_CLKVDD") (class "Default")
      (node (ref "C53") (pin "1") (pinfunction "1_1") (pintype "passive"))
      (node (ref "C56") (pin "1") (pinfunction "1_1") (pintype "passive"))
      (node (ref "IC10") (pin "44") (pinfunction "CLKVDD_44") (pintype "input"))
      (node (ref "J2") (pin "1") (pinfunction "1_1") (pintype "passive"))
    )
    (net (code "19") (name "ADC_CS") (class "Default")
      (node (ref "IC10") (pin "1") (pinfunction "FORMAT0/CS_1") (pintype "input"))
      (node (ref "R49") (pin "1") (pinfunction "1_1") (pintype "passive"))
    )
    (net (code "20") (name "ADC_DCLK") (class "Default")
      (node (ref "IC10") (pin "11") (pinfunction "DCLK_11") (pintype "bidirectional"))
      (node (ref "R47") (pin "1") (pinfunction "1_1") (pintype "passive"))
    )
    (net (code "21") (name "ADC_DOUT") (class "Default")
      (node (ref "IC10") (pin "10") (pinfunction "DOUT0_10") (pintype "output"))
      (node (ref "R46") (pin "1") (pinfunction "1_1") (pintype "passive"))
    )
    (net (code "22") (name "ADC_DVDD1V8") (class "Default")
      (node (ref "C58") (pin "1") (pinfunction "1_1") (pintype "passive"))
      (node (ref "C60") (pin "1") (pinfunction "1_1") (pintype "passive"))
      (node (ref "IC10") (pin "20") (pinfunction "DVDD1V8_20") (pintype "input"))
    )
    (net (code "23") (name "ADC_ODR") (class "Default")
      (node (ref "IC10") (pin "12") (pinfunction "ODR_12") (pintype "bidirectional"))
      (node (ref "R45") (pin "1") (pinfunction "1_1") (pintype "passive"))
    )
    (net (code "24") (name "ADC_SCLK") (class "Default")
      (node (ref "IC10") (pin "2") (pinfunction "FORMAT1/SCLK_2") (pintype "input"))
      (node (ref "R50") (pin "1") (pinfunction "1_1") (pintype "passive"))
    )
    (net (code "25") (name "ADC_SDI") (class "Default")
      (node (ref "IC10") (pin "4") (pinfunction "DEC2/SDI_4") (pintype "input"))
      (node (ref "R51") (pin "1") (pinfunction "1_1") (pintype "passive"))
    )
    (net (code "26") (name "ADC_SDO") (class "Default")
      (node (ref "IC10") (pin "3") (pinfunction "DEC3/SDO_3") (pintype "bidirectional"))
      (node (ref "R44") (pin "2") (pinfunction "2_2") (pintype "passive"))
      (node (ref "R48") (pin "1") (pinfunction "1_1") (pintype "passive"))
    )
    (net (code "27") (name "ADC_VCOM") (class "Default")
      (node (ref "C40") (pin "2") (pinfunction "2_2") (pintype "passive"))
      (node (ref "R1") (pin "2") (pinfunction "2_2") (pintype "passive"))
      (node (ref "R14") (pin "1") (pinfunction "1_1") (pintype "passive"))
      (node (ref "R2") (pin "1") (pinfunction "1_1") (pintype "passive"))
      (node (ref "R25") (pin "1") (pinfunction "1_1") (pintype "passive"))
      (node (ref "TP22") (pin "1") (pinfunction "1_1") (pintype "passive"))
    )
    (net (code "28") (name "AVDD5V") (class "Default")
      (node (ref "C41") (pin "1") (pinfunction "1_1") (pintype "passive"))
      (node (ref "C43") (pin "1") (pinfunction "1_1") (pintype "passive"))
      (node (ref "C48") (pin "1") (pinfunction "1_1") (pintype "passive"))
      (node (ref "C49") (pin "1") (pinfunction "1_1") (pintype "passive"))
      (node (ref "D1") (pin "2") (pinfunction "C_2") (pintype "bidirectional"))
      (node (ref "IC10") (pin "26") (pinfunction "AVDD5_26") (pintype "input"))
      (node (ref "IC11") (pin "2") (pinfunction "VIN_2") (pintype "input"))
      (node (ref "IC9") (pin "1") (pinfunction "VOUT2_1") (pintype "output"))
    )
    (net (code "29") (name "DGND") (class "Default")
      (node (ref "C3") (pin "2") (pinfunction "2_2") (pintype "passive"))
      (node (ref "C6") (pin "2") (pinfunction "2_2") (pintype "passive"))
      (node (ref "C75") (pin "2") (pinfunction "2_2") (pintype "passive"))
      (node (ref "C76") (pin "2") (pinfunction "2_2") (pintype "passive"))
      (node (ref "C77") (pin "2") (pinfunction "2_2") (pintype "passive"))
      (node (ref "C78") (pin "2") (pinfunction "2_2") (pintype "passive"))
      (node (ref "C79") (pin "2") (pinfunction "2_2") (pintype "passive"))
      (node (ref "FB1") (pin "1") (pinfunction "1_1") (pintype "passive"))
      (node (ref "IC1") (pin "1") (pinfunction "GND_1") (pintype "bidirectional"))
      (node (ref "IC1") (pin "101") (pinfunction "GND_101") (pintype "bidirectional"))
      (node (ref "IC1") (pin "102") (pinfunction "GND_102") (pintype "bidirectional"))
      (node (ref "IC1") (pin "103") (pinfunction "GND_103") (pintype "bidirectional"))
      (node (ref "IC1") (pin "104") (pinfunction "GND_104") (pintype "bidirectional"))
      (node (ref "IC1") (pin "113") (pinfunction "GND_113") (pintype "bidirectional"))
      (node (ref "IC1") (pin "114") (pinfunction "GND_114") (pintype "bidirectional"))
      (node (ref "IC1") (pin "115") (pinfunction "GND_115") (pintype "bidirectional"))
      (node (ref "IC1") (pin "116") (pinfunction "GND_116") (pintype "bidirectional"))
      (node (ref "IC1") (pin "2") (pinfunction "GND_2") (pintype "bidirectional"))
      (node (ref "IC1") (pin "39") (pinfunction "GND_39") (pintype "bidirectional"))
      (node (ref "IC1") (pin "40") (pinfunction "GND_40") (pintype "bidirectional"))
      (node (ref "IC1") (pin "53") (pinfunction "GND_53") (pintype "bidirectional"))
      (node (ref "IC1") (pin "54") (pinfunction "GND_54") (pintype "bidirectional"))
      (node (ref "IC1") (pin "57") (pinfunction "GND_57") (pintype "bidirectional"))
      (node (ref "IC1") (pin "58") (pinfunction "GND_58") (pintype "bidirectional"))
      (node (ref "IC1") (pin "61") (pinfunction "GND_61") (pintype "bidirectional"))
      (node (ref "IC1") (pin "62") (pinfunction "GND_62") (pintype "bidirectional"))
      (node (ref "IC1") (pin "83") (pinfunction "GND_83") (pintype "bidirectional"))
      (node (ref "IC1") (pin "84") (pinfunction "GND_84") (pintype "bidirectional"))
      (node (ref "IC15") (pin "5") (pinfunction "GND2_5") (pintype "power_in"))
      (node (ref "IC16") (pin "5") (pinfunction "GND2_5") (pintype "power_in"))
      (node (ref "IC17") (pin "4") (pinfunction "GND1_4") (pintype "power_in"))
      (node (ref "IC18") (pin "4") (pinfunction "GND1_4") (pintype "power_in"))
      (node (ref "IC2") (pin "2") (pinfunction "GND_2") (pintype "input"))
      (node (ref "IC2") (pin "3") (pinfunction "~{EN}_3") (pintype "input"))
      (node (ref "R53") (pin "2") (pinfunction "2_2") (pintype "passive"))
      (node (ref "R7") (pin "1") (pinfunction "1_1") (pintype "passive"))
      (node (ref "SW2") (pin "5") (pinfunction "B4_5") (pintype "passive"))
      (node (ref "SW2") (pin "6") (pinfunction "B3_6") (pintype "passive"))
      (node (ref "SW2") (pin "7") (pinfunction "B2_7") (pintype "passive"))
      (node (ref "SW2") (pin "8") (pinfunction "B1_8") (pintype "passive"))
      (node (ref "TP13") (pin "1") (pinfunction "1_1") (pintype "passive"))
    )
    (net (code "30") (name "DIPSW1") (class "Default")
      (node (ref "IC1") (pin "86") (pinfunction "IO0_14/K12_86") (pintype "bidirectional"))
      (node (ref "R63") (pin "1") (pinfunction "1_1") (pintype "passive"))
      (node (ref "SW2") (pin "1") (pinfunction "A1_1") (pintype "passive"))
    )
    (net (code "31") (name "DIPSW2") (class "Default")
      (node (ref "IC1") (pin "88") (pinfunction "IO5P_14/K13_88") (pintype "bidirectional"))
      (node (ref "R64") (pin "1") (pinfunction "1_1") (pintype "passive"))
      (node (ref "SW2") (pin "2") (pinfunction "A2_2") (pintype "passive"))
    )
    (net (code "32") (name "DIPSW3") (class "Default")
      (node (ref "IC1") (pin "90") (pinfunction "IO12P_14/N14_90") (pintype "bidirectional"))
      (node (ref "R65") (pin "1") (pinfunction "1_1") (pintype "passive"))
      (node (ref "SW2") (pin "3") (pinfunction "A3_3") (pintype "passive"))
    )
    (net (code "33") (name "DIPSW4") (class "Default")
      (node (ref "IC1") (pin "92") (pinfunction "IO12N_14/P14_92") (pintype "bidirectional"))
      (node (ref "R66") (pin "1") (pinfunction "1_1") (pintype "passive"))
      (node (ref "SW2") (pin "4") (pinfunction "A4_4") (pintype "passive"))
    )
    (net (code "34") (name "FPGA_CS") (class "Default")
      (node (ref "IC1") (pin "38") (pinfunction "IO23N_35/L2_38") (pintype "bidirectional"))
      (node (ref "R59") (pin "2") (pinfunction "2_2") (pintype "passive"))
    )
    (net (code "35") (name "FPGA_DCLK") (class "Default")
      (node (ref "IC1") (pin "52") (pinfunction "IO7P_34/R2_52") (pintype "bidirectional"))
      (node (ref "R57") (pin "2") (pinfunction "2_2") (pintype "passive"))
    )
    (net (code "36") (name "FPGA_DCLK_SUB") (class "Default")
      (node (ref "IC1") (pin "21") (pinfunction "IO12P_35/D4_21") (pintype "bidirectional"))
      (node (ref "R56") (pin "2") (pinfunction "2_2") (pintype "passive"))
    )
    (net (code "37") (name "FPGA_DOUT") (class "Default")
      (node (ref "IC1") (pin "50") (pinfunction "IO7N_34/R1_50") (pintype "bidirectional"))
      (node (ref "R55") (pin "2") (pinfunction "2_2") (pintype "passive"))
    )
    (net (code "38") (name "FPGA_LED") (class "Default")
      (node (ref "IC1") (pin "42") (pinfunction "IO2N_34/M1_42") (pintype "bidirectional"))
      (node (ref "R62") (pin "2") (pinfunction "2_2") (pintype "passive"))
    )
    (net (code "39") (name "FPGA_ODR") (class "Default")
      (node (ref "IC1") (pin "48") (pinfunction "IO4N_34/P1_48") (pintype "bidirectional"))
      (node (ref "R54") (pin "2") (pinfunction "2_2") (pintype "passive"))
    )
    (net (code "40") (name "FPGA_SCLK") (class "Default")
      (node (ref "IC1") (pin "36") (pinfunction "IO23P_35/L3_36") (pintype "bidirectional"))
      (node (ref "R60") (pin "2") (pinfunction "2_2") (pintype "passive"))
    )
    (net (code "41") (name "FPGA_SDI") (class "Default")
      (node (ref "IC1") (pin "44") (pinfunction "IO2P_34/M2_44") (pintype "bidirectional"))
      (node (ref "R61") (pin "2") (pinfunction "2_2") (pintype "passive"))
    )
    (net (code "42") (name "FPGA_SDO") (class "Default")
      (node (ref "IC1") (pin "34") (pinfunction "IO22P_35/K1_34") (pintype "bidirectional"))
      (node (ref "R58") (pin "2") (pinfunction "2_2") (pintype "passive"))
    )
    (net (code "43") (name "GND") (class "Default")
      (node (ref "C13") (pin "2") (pinfunction "2_2") (pintype "passive"))
      (node (ref "C14") (pin "2") (pinfunction "2_2") (pintype "passive"))
      (node (ref "C15") (pin "-") (pinfunction "2_-") (pintype "passive"))
      (node (ref "C16") (pin "2") (pinfunction "2_2") (pintype "passive"))
      (node (ref "C17") (pin "1") (pinfunction "1_1") (pintype "passive"))
      (node (ref "C18") (pin "-") (pinfunction "2_-") (pintype "passive"))
      (node (ref "C19") (pin "2") (pinfunction "2_2") (pintype "passive"))
      (node (ref "C20") (pin "2") (pinfunction "2_2") (pintype "passive"))
      (node (ref "C21") (pin "-") (pinfunction "2_-") (pintype "passive"))
      (node (ref "C22") (pin "+") (pinfunction "1_+") (pintype "passive"))
      (node (ref "C23") (pin "2") (pinfunction "2_2") (pintype "passive"))
      (node (ref "C24") (pin "2") (pinfunction "2_2") (pintype "passive"))
      (node (ref "C25") (pin "2") (pinfunction "2_2") (pintype "passive"))
      (node (ref "C26") (pin "1") (pinfunction "1_1") (pintype "passive"))
      (node (ref "C27") (pin "1") (pinfunction "1_1") (pintype "passive"))
      (node (ref "C28") (pin "2") (pinfunction "2_2") (pintype "passive"))
      (node (ref "C29") (pin "1") (pinfunction "1_1") (pintype "passive"))
      (node (ref "C30") (pin "2") (pinfunction "2_2") (pintype "passive"))
      (node (ref "C31") (pin "1") (pinfunction "1_1") (pintype "passive"))
      (node (ref "C32") (pin "1") (pinfunction "1_1") (pintype "passive"))
      (node (ref "C33") (pin "2") (pinfunction "2_2") (pintype "passive"))
      (node (ref "C34") (pin "1") (pinfunction "1_1") (pintype "passive"))
      (node (ref "C35") (pin "-") (pinfunction "2_-") (pintype "passive"))
      (node (ref "C36") (pin "+") (pinfunction "1_+") (pintype "passive"))
      (node (ref "C37") (pin "+") (pinfunction "1_+") (pintype "passive"))
      (node (ref "C38") (pin "2") (pinfunction "2_2") (pintype "passive"))
      (node (ref "C39") (pin "2") (pinfunction "2_2") (pintype "passive"))
      (node (ref "C4") (pin "1") (pinfunction "1_1") (pintype "passive"))
      (node (ref "C40") (pin "1") (pinfunction "1_1") (pintype "passive"))
      (node (ref "C41") (pin "2") (pinfunction "2_2") (pintype "passive"))
      (node (ref "C42") (pin "2") (pinfunction "2_2") (pintype "passive"))
      (node (ref "C43") (pin "2") (pinfunction "2_2") (pintype "passive"))
      (node (ref "C44") (pin "-") (pinfunction "2_-") (pintype "passive"))
      (node (ref "C45") (pin "2") (pinfunction "2_2") (pintype "passive"))
      (node (ref "C46") (pin "2") (pinfunction "2_2") (pintype "passive"))
      (node (ref "C47") (pin "2") (pinfunction "2_2") (pintype "passive"))
      (node (ref "C48") (pin "2") (pinfunction "2_2") (pintype "passive"))
      (node (ref "C49") (pin "2") (pinfunction "2_2") (pintype "passive"))
      (node (ref "C5") (pin "2") (pinfunction "2_2") (pintype "passive"))
      (node (ref "C50") (pin "2") (pinfunction "2_2") (pintype "passive"))
      (node (ref "C51") (pin "2") (pinfunction "2_2") (pintype "passive"))
      (node (ref "C52") (pin "2") (pinfunction "2_2") (pintype "passive"))
      (node (ref "C53") (pin "2") (pinfunction "2_2") (pintype "passive"))
      (node (ref "C54") (pin "2") (pinfunction "2_2") (pintype "passive"))
      (node (ref "C55") (pin "2") (pinfunction "2_2") (pintype "passive"))
      (node (ref "C56") (pin "2") (pinfunction "2_2") (pintype "passive"))
      (node (ref "C57") (pin "2") (pinfunction "2_2") (pintype "passive"))
      (node (ref "C58") (pin "2") (pinfunction "2_2") (pintype "passive"))
      (node (ref "C59") (pin "2") (pinfunction "2_2") (pintype "passive"))
      (node (ref "C60") (pin "2") (pinfunction "2_2") (pintype "passive"))
      (node (ref "C61") (pin "2") (pinfunction "2_2") (pintype "passive"))
      (node (ref "C62") (pin "2") (pinfunction "2_2") (pintype "passive"))
      (node (ref "C63") (pin "2") (pinfunction "2_2") (pintype "passive"))
      (node (ref "C64") (pin "2") (pinfunction "2_2") (pintype "passive"))
      (node (ref "C65") (pin "2") (pinfunction "2_2") (pintype "passive"))
      (node (ref "C66") (pin "2") (pinfunction "2_2") (pintype "passive"))
      (node (ref "C67") (pin "2") (pinfunction "2_2") (pintype "passive"))
      (node (ref "C68") (pin "2") (pinfunction "2_2") (pintype "passive"))
      (node (ref "C69") (pin "2") (pinfunction "2_2") (pintype "passive"))
      (node (ref "C7") (pin "1") (pinfunction "1_1") (pintype "passive"))
      (node (ref "C70") (pin "2") (pinfunction "2_2") (pintype "passive"))
      (node (ref "C71") (pin "2") (pinfunction "2_2") (pintype "passive"))
      (node (ref "C72") (pin "2") (pinfunction "2_2") (pintype "passive"))
      (node (ref "C73") (pin "2") (pinfunction "2_2") (pintype "passive"))
      (node (ref "C74") (pin "2") (pinfunction "2_2") (pintype "passive"))
      (node (ref "C9") (pin "2") (pinfunction "2_2") (pintype "passive"))
      (node (ref "CON1") (pin "G1") (pinfunction "GND_G1") (pintype "passive"))
      (node (ref "CON1") (pin "G2") (pinfunction "GND_G2") (pintype "passive"))
      (node (ref "CON1") (pin "G3") (pinfunction "GND_G3") (pintype "passive"))
      (node (ref "CON1") (pin "G4") (pinfunction "GND_G4") (pintype "passive"))
      (node (ref "CON2") (pin "G1") (pinfunction "GND_G1") (pintype "passive"))
      (node (ref "CON2") (pin "G2") (pinfunction "GND_G2") (pintype "passive"))
      (node (ref "CON2") (pin "G3") (pinfunction "GND_G3") (pintype "passive"))
      (node (ref "CON2") (pin "G4") (pinfunction "GND_G4") (pintype "passive"))
      (node (ref "D1") (pin "1") (pinfunction "A_1") (pintype "bidirectional"))
      (node (ref "D2") (pin "K") (pinfunction "K_K") (pintype "passive"))
      (node (ref "D3") (pin "K") (pinfunction "K_K") (pintype "passive"))
      (node (ref "IC10") (pin "14") (pinfunction "IOGND_14") (pintype "input"))
      (node (ref "IC10") (pin "19") (pinfunction "DGND1V8_19") (pintype "input"))
      (node (ref "IC10") (pin "22") (pinfunction "AGND1V8_22") (pintype "input"))
      (node (ref "IC10") (pin "24") (pinfunction "DGND5_24") (pintype "input"))
      (node (ref "IC10") (pin "27") (pinfunction "AGND5_27") (pintype "input"))
      (node (ref "IC10") (pin "31") (pinfunction "AGND5_31") (pintype "input"))
      (node (ref "IC10") (pin "37") (pinfunction "REFGND_37") (pintype "input"))
      (node (ref "IC10") (pin "40") (pinfunction "AGND5_40") (pintype "input"))
      (node (ref "IC10") (pin "43") (pinfunction "CLKGND_43") (pintype "input"))
      (node (ref "IC10") (pin "HT") (pinfunction "AGND5_HT") (pintype "input"))
      (node (ref "IC10") (pin "HT1") (pinfunction "AGND5_HT1") (pintype "input"))
      (node (ref "IC10") (pin "HT2") (pinfunction "AGND5_HT2") (pintype "input"))
      (node (ref "IC10") (pin "HT3") (pinfunction "AGND5_HT3") (pintype "input"))
      (node (ref "IC10") (pin "HT4") (pinfunction "AGND5_HT4") (pintype "input"))
      (node (ref "IC11") (pin "4") (pinfunction "GND_4") (pintype "input"))
      (node (ref "IC12") (pin "2") (pinfunction "GND_2") (pintype "input"))
      (node (ref "IC13") (pin "2") (pinfunction "GND_2") (pintype "input"))
      (node (ref "IC14") (pin "2") (pinfunction "GND_2") (pintype "input"))
      (node (ref "IC15") (pin "4") (pinfunction "GND1_4") (pintype "power_in"))
      (node (ref "IC16") (pin "4") (pinfunction "GND1_4") (pintype "power_in"))
      (node (ref "IC17") (pin "5") (pinfunction "GND2_5") (pintype "power_in"))
      (node (ref "IC18") (pin "5") (pinfunction "GND2_5") (pintype "power_in"))
      (node (ref "IC5") (pin "2") (pinfunction "GND_2") (pintype "input"))
      (node (ref "IC9") (pin "10") (pinfunction "GND2_10") (pintype "input"))
      (node (ref "IC9") (pin "6") (pinfunction "GND1_6") (pintype "input"))
      (node (ref "IC9") (pin "8") (pinfunction "GND_REG_8") (pintype "input"))
      (node (ref "IC9") (pin "HT") (pinfunction "HT_HT") (pintype "passive"))
      (node (ref "IC9") (pin "HT2") (pinfunction "HT_HT2") (pintype "passive"))
      (node (ref "J2") (pin "3") (pinfunction "3_3") (pintype "passive"))
      (node (ref "R19") (pin "1") (pinfunction "1_1") (pintype "passive"))
      (node (ref "R20") (pin "2") (pinfunction "2_2") (pintype "passive"))
      (node (ref "R21") (pin "2") (pinfunction "2_2") (pintype "passive"))
      (node (ref "R41") (pin "1") (pinfunction "1_1") (pintype "passive"))
      (node (ref "R44") (pin "1") (pinfunction "1_1") (pintype "passive"))
      (node (ref "R53") (pin "1") (pinfunction "1_1") (pintype "passive"))
      (node (ref "SW1") (pin "HT1") (pinfunction "SHIELD_HT1") (pintype "passive"))
      (node (ref "SW1") (pin "HT2") (pinfunction "SHIELD_HT2") (pintype "passive"))
      (node (ref "TP1") (pin "1") (pinfunction "1_1") (pintype "passive"))
      (node (ref "TP10") (pin "1") (pinfunction "1_1") (pintype "passive"))
      (node (ref "TP11") (pin "1") (pinfunction "1_1") (pintype "passive"))
      (node (ref "TP12") (pin "1") (pinfunction "1_1") (pintype "passive"))
      (node (ref "TP14") (pin "1") (pinfunction "1_1") (pintype "passive"))
      (node (ref "TP15") (pin "1") (pinfunction "1_1") (pintype "passive"))
      (node (ref "TP19") (pin "1") (pinfunction "1_1") (pintype "passive"))
      (node (ref "TP20") (pin "1") (pinfunction "1_1") (pintype "passive"))
      (node (ref "TP21") (pin "1") (pinfunction "1_1") (pintype "passive"))
      (node (ref "TP3") (pin "1") (pinfunction "1_1") (pintype "passive"))
      (node (ref "TP4") (pin "1") (pinfunction "1_1") (pintype "passive"))
      (node (ref "TP5") (pin "1") (pinfunction "1_1") (pintype "passive"))
      (node (ref "TP7") (pin "1") (pinfunction "1_1") (pintype "passive"))
      (node (ref "TP8") (pin "1") (pinfunction "1_1") (pintype "passive"))
      (node (ref "TP9") (pin "1") (pinfunction "1_1") (pintype "passive"))
      (node (ref "U1") (pin "GND1") (pinfunction "GND1_GND1") (pintype "power_in"))
      (node (ref "U1") (pin "GND2") (pinfunction "GND2_GND2") (pintype "power_in"))
      (node (ref "X1") (pin "2") (pinfunction "GND_2") (pintype "input"))
      (node (ref "X1") (pin "2-2") (pinfunction "GND_2-2") (pintype "input"))
    )
    (net (code "44") (name "Net-(C1-Pad1)") (class "Default")
      (node (ref "C1") (pin "1") (pinfunction "1_1") (pintype "passive"))
      (node (ref "CON1") (pin "SIG") (pinfunction "SIG_SIG") (pintype "passive"))
      (node (ref "SW1") (pin "C2") (pinfunction "C2_C2") (pintype "passive"))
      (node (ref "TP2") (pin "1") (pinfunction "1_1") (pintype "passive"))
    )
    (net (code "45") (name "Net-(C1-Pad2)") (class "Default")
      (node (ref "C1") (pin "2") (pinfunction "2_2") (pintype "passive"))
      (node (ref "R1") (pin "1") (pinfunction "1_1") (pintype "passive"))
      (node (ref "R3") (pin "1") (pinfunction "1_1") (pintype "passive"))
      (node (ref "SW1") (pin "A2") (pinfunction "A2_A2") (pintype "passive"))
    )
    (net (code "46") (name "Net-(C2-Pad1)") (class "Default")
      (node (ref "C2") (pin "1") (pinfunction "1_1") (pintype "passive"))
      (node (ref "CON2") (pin "SIG") (pinfunction "SIG_SIG") (pintype "passive"))
      (node (ref "SW1") (pin "C1") (pinfunction "C1_C1") (pintype "passive"))
      (node (ref "TP6") (pin "1") (pinfunction "1_1") (pintype "passive"))
    )
    (net (code "47") (name "Net-(C2-Pad2)") (class "Default")
      (node (ref "C2") (pin "2") (pinfunction "2_2") (pintype "passive"))
      (node (ref "R2") (pin "2") (pinfunction "2_2") (pintype "passive"))
      (node (ref "R4") (pin "1") (pinfunction "1_1") (pintype "passive"))
      (node (ref "SW1") (pin "A1") (pinfunction "A1_A1") (pintype "passive"))
    )
    (net (code "48") (name "Net-(C4-Pad2)") (class "Default")
      (node (ref "C4") (pin "2") (pinfunction "2_2") (pintype "passive"))
      (node (ref "R5") (pin "2") (pinfunction "2_2") (pintype "passive"))
    )
    (net (code "49") (name "Net-(C5-Pad1)") (class "Default")
      (node (ref "C5") (pin "1") (pinfunction "1_1") (pintype "passive"))
      (node (ref "R6") (pin "1") (pinfunction "1_1") (pintype "passive"))
    )
    (net (code "50") (name "Net-(D2-PadA)") (class "Default")
      (node (ref "D2") (pin "A") (pinfunction "A_A") (pintype "passive"))
      (node (ref "R43") (pin "1") (pinfunction "1_1") (pintype "passive"))
    )
    (net (code "51") (name "Net-(D3-PadA)") (class "Default")
      (node (ref "D3") (pin "A") (pinfunction "A_A") (pintype "passive"))
      (node (ref "R52") (pin "1") (pinfunction "1_1") (pintype "passive"))
    )
    (net (code "52") (name "Net-(FB1-Pad2)") (class "Default")
      (node (ref "FB1") (pin "2") (pinfunction "2_2") (pintype "passive"))
      (node (ref "FB3") (pin "1") (pinfunction "1_1") (pintype "passive"))
    )
    (net (code "53") (name "Net-(FB2-Pad2)") (class "Default")
      (node (ref "FB2") (pin "2") (pinfunction "2_2") (pintype "passive"))
      (node (ref "TP30") (pin "1") (pinfunction "1_1") (pintype "passive"))
      (node (ref "U1") (pin "VIN+") (pinfunction "VIN+_VIN+") (pintype "power_in"))
    )
    (net (code "54") (name "Net-(FB3-Pad2)") (class "Default")
      (node (ref "FB3") (pin "2") (pinfunction "2_2") (pintype "passive"))
      (node (ref "TP31") (pin "1") (pinfunction "1_1") (pintype "passive"))
      (node (ref "U1") (pin "VIN-") (pinfunction "VIN-_VIN-") (pintype "power_in"))
    )
    (net (code "55") (name "Net-(FB4-Pad2)") (class "Default")
      (node (ref "FB4") (pin "2") (pinfunction "2_2") (pintype "passive"))
      (node (ref "U1") (pin "+5V") (pinfunction "+5V_+5V") (pintype "output"))
    )
    (net (code "56") (name "Net-(FB5-Pad1)") (class "Default")
      (node (ref "FB5") (pin "1") (pinfunction "1_1") (pintype "passive"))
      (node (ref "U1") (pin "V+") (pinfunction "V+_V+") (pintype "output"))
    )
    (net (code "57") (name "Net-(FB6-Pad1)") (class "Default")
      (node (ref "FB6") (pin "1") (pinfunction "1_1") (pintype "passive"))
      (node (ref "U1") (pin "V-") (pinfunction "V-_V-") (pintype "output"))
    )
    (net (code "58") (name "Net-(IC2-ILIM)") (class "Default")
      (node (ref "IC2") (pin "5") (pinfunction "ILIM_5") (pintype "passive"))
      (node (ref "R7") (pin "2") (pinfunction "2_2") (pintype "passive"))
    )
    (net (code "59") (name "Net-(IC3A-+IN)") (class "Default")
      (node (ref "IC3") (pin "3") (pinfunction "+IN_3") (pintype "input"))
      (node (ref "R17") (pin "2") (pinfunction "2_2") (pintype "passive"))
      (node (ref "R18") (pin "2") (pinfunction "2_2") (pintype "passive"))
    )
    (net (code "60") (name "Net-(IC3A--IN)") (class "Default")
      (node (ref "C10") (pin "2") (pinfunction "2_2") (pintype "passive"))
      (node (ref "IC3") (pin "4") (pinfunction "-IN_4") (pintype "input"))
      (node (ref "R14") (pin "2") (pinfunction "2_2") (pintype "passive"))
    )
    (net (code "61") (name "Net-(IC3A-OUT)") (class "Default")
      (node (ref "C10") (pin "1") (pinfunction "1_1") (pintype "passive"))
      (node (ref "IC3") (pin "1") (pinfunction "OUT_1") (pintype "output"))
      (node (ref "R8") (pin "2") (pinfunction "2_2") (pintype "passive"))
      (node (ref "R9") (pin "2") (pinfunction "2_2") (pintype "passive"))
    )
    (net (code "62") (name "Net-(IC3B-V-)") (class "Default")
      (node (ref "C34") (pin "2") (pinfunction "2_2") (pintype "passive"))
      (node (ref "IC3") (pin "2") (pinfunction "V-_2") (pintype "input"))
      (node (ref "J1") (pin "2") (pinfunction "2_2") (pintype "passive"))
    )
    (net (code "63") (name "Net-(IC4A-+IN)") (class "Default")
      (node (ref "C7") (pin "2") (pinfunction "2_2") (pintype "passive"))
      (node (ref "C8") (pin "1") (pinfunction "1_1") (pintype "passive"))
      (node (ref "IC4") (pin "3") (pinfunction "+IN_3") (pintype "input"))
      (node (ref "R3") (pin "2") (pinfunction "2_2") (pintype "passive"))
      (node (ref "R5") (pin "1") (pinfunction "1_1") (pintype "passive"))
    )
    (net (code "64") (name "Net-(IC4A--IN)") (class "Default")
      (node (ref "C11") (pin "1") (pinfunction "1_1") (pintype "passive"))
      (node (ref "IC4") (pin "2") (pinfunction "-IN_2") (pintype "input"))
      (node (ref "R10") (pin "2") (pinfunction "2_2") (pintype "passive"))
      (node (ref "R12") (pin "1") (pinfunction "1_1") (pintype "passive"))
    )
    (net (code "65") (name "Net-(IC4A-OUT)") (class "Default")
      (node (ref "C11") (pin "2") (pinfunction "2_2") (pintype "passive"))
      (node (ref "IC4") (pin "1") (pinfunction "OUT_1") (pintype "output"))
      (node (ref "R15") (pin "1") (pinfunction "1_1") (pintype "passive"))
    )
    (net (code "66") (name "Net-(IC4B-+IN)") (class "Default")
      (node (ref "C8") (pin "2") (pinfunction "2_2") (pintype "passive"))
      (node (ref "C9") (pin "1") (pinfunction "1_1") (pintype "passive"))
      (node (ref "IC4") (pin "5") (pinfunction "+IN_5") (pintype "input"))
      (node (ref "R4") (pin "2") (pinfunction "2_2") (pintype "passive"))
      (node (ref "R6") (pin "2") (pinfunction "2_2") (pintype "passive"))
    )
    (net (code "67") (name "Net-(IC4B--IN)") (class "Default")
      (node (ref "C12") (pin "1") (pinfunction "1_1") (pintype "passive"))
      (node (ref "IC4") (pin "6") (pinfunction "-IN_6") (pintype "input"))
      (node (ref "R11") (pin "2") (pinfunction "2_2") (pintype "passive"))
      (node (ref "R13") (pin "1") (pinfunction "1_1") (pintype "passive"))
    )
    (net (code "68") (name "Net-(IC4B-OUT)") (class "Default")
      (node (ref "C12") (pin "2") (pinfunction "2_2") (pintype "passive"))
      (node (ref "IC4") (pin "7") (pinfunction "OUT_7") (pintype "output"))
      (node (ref "R16") (pin "1") (pinfunction "1_1") (pintype "passive"))
    )
    (net (code "69") (name "Net-(IC6-ADJ)") (class "Default")
      (node (ref "C30") (pin "1") (pinfunction "1_1") (pintype "passive"))
      (node (ref "IC6") (pin "1") (pinfunction "ADJ_1") (pintype "input"))
      (node (ref "R19") (pin "2") (pinfunction "2_2") (pintype "passive"))
      (node (ref "R22") (pin "1") (pinfunction "1_1") (pintype "passive"))
    )
    (net (code "70") (name "Net-(IC7-ADJ)") (class "Default")
      (node (ref "C31") (pin "2") (pinfunction "2_2") (pintype "passive"))
      (node (ref "IC7") (pin "1") (pinfunction "ADJ_1") (pintype "input"))
      (node (ref "R20") (pin "1") (pinfunction "1_1") (pintype "passive"))
      (node (ref "R23") (pin "1") (pinfunction "1_1") (pintype "passive"))
    )
    (net (code "71") (name "Net-(IC8-ADJ)") (class "Default")
      (node (ref "C32") (pin "2") (pinfunction "2_2") (pintype "passive"))
      (node (ref "IC8") (pin "1") (pinfunction "ADJ_1") (pintype "input"))
      (node (ref "R21") (pin "1") (pinfunction "1_1") (pintype "passive"))
      (node (ref "R24") (pin "1") (pinfunction "1_1") (pintype "passive"))
    )
    (net (code "72") (name "Net-(IC9-NP1)") (class "Default")
      (node (ref "C47") (pin "1") (pinfunction "1_1") (pintype "passive"))
      (node (ref "IC9") (pin "7") (pinfunction "NP1_7") (pintype "passive"))
    )
    (net (code "73") (name "Net-(IC9-NP2)") (class "Default")
      (node (ref "C46") (pin "1") (pinfunction "1_1") (pintype "passive"))
      (node (ref "IC9") (pin "9") (pinfunction "NP2_9") (pintype "passive"))
    )
    (net (code "74") (name "Net-(IC10-AIN0+)") (class "Default")
      (node (ref "IC10") (pin "29") (pinfunction "AIN0+_29") (pintype "input"))
      (node (ref "R26") (pin "2") (pinfunction "2_2") (pintype "passive"))
    )
    (net (code "75") (name "Net-(IC10-AIN0-)") (class "Default")
      (node (ref "IC10") (pin "30") (pinfunction "AIN0-_30") (pintype "input"))
      (node (ref "R27") (pin "2") (pinfunction "2_2") (pintype "passive"))
    )
    (net (code "76") (name "Net-(IC10-AIN1+)") (class "Default")
      (node (ref "IC10") (pin "32") (pinfunction "AIN1+_32") (pintype "input"))
      (node (ref "R28") (pin "2") (pinfunction "2_2") (pintype "passive"))
    )
    (net (code "77") (name "Net-(IC10-AIN1-)") (class "Default")
      (node (ref "IC10") (pin "33") (pinfunction "AIN1-_33") (pintype "input"))
      (node (ref "R29") (pin "2") (pinfunction "2_2") (pintype "passive"))
    )
    (net (code "78") (name "Net-(IC10-AIN2+)") (class "Default")
      (node (ref "IC10") (pin "38") (pinfunction "AIN2+_38") (pintype "input"))
      (node (ref "R30") (pin "2") (pinfunction "2_2") (pintype "passive"))
    )
    (net (code "79") (name "Net-(IC10-AIN2-)") (class "Default")
      (node (ref "IC10") (pin "39") (pinfunction "AIN2-_39") (pintype "input"))
      (node (ref "R31") (pin "2") (pinfunction "2_2") (pintype "passive"))
    )
    (net (code "80") (name "Net-(IC10-AIN3+)") (class "Default")
      (node (ref "IC10") (pin "41") (pinfunction "AIN3+_41") (pintype "input"))
      (node (ref "R32") (pin "2") (pinfunction "2_2") (pintype "passive"))
    )
    (net (code "81") (name "Net-(IC10-AIN3-)") (class "Default")
      (node (ref "IC10") (pin "42") (pinfunction "AIN3-_42") (pintype "input"))
      (node (ref "R33") (pin "2") (pinfunction "2_2") (pintype "passive"))
    )
    (net (code "82") (name "Net-(IC10-CLKSEL)") (class "Default")
      (node (ref "IC10") (pin "47") (pinfunction "CLKSEL_47") (pintype "input"))
      (node (ref "J2") (pin "2") (pinfunction "2_2") (pintype "passive"))
    )
    (net (code "83") (name "Net-(IC10-DEC0{slash}DCLKIO)") (class "Default")
      (node (ref "IC10") (pin "6") (pinfunction "DEC0/DCLKIO_6") (pintype "input"))
      (node (ref "R36") (pin "1") (pinfunction "1_1") (pintype "passive"))
    )
    (net (code "84") (name "Net-(IC10-DEC1{slash}DCLKMODE)") (class "Default")
      (node (ref "IC10") (pin "5") (pinfunction "DEC1/DCLKMODE_5") (pintype "input"))
      (node (ref "R37") (pin "1") (pinfunction "1_1") (pintype "passive"))
    )
    (net (code "85") (name "Net-(IC10-MODE)") (class "Default")
      (node (ref "IC10") (pin "50") (pinfunction "MODE_50") (pintype "input"))
      (node (ref "R39") (pin "1") (pinfunction "1_1") (pintype "passive"))
    )
    (net (code "86") (name "Net-(IC10-PIN{slash}SPI)") (class "Default")
      (node (ref "IC10") (pin "49") (pinfunction "PIN/SPI_49") (pintype "input"))
      (node (ref "R38") (pin "1") (pinfunction "1_1") (pintype "passive"))
    )
    (net (code "87") (name "Net-(IC10-VCM)") (class "Default")
      (node (ref "IC10") (pin "34") (pinfunction "VCM_34") (pintype "bidirectional"))
      (node (ref "R25") (pin "2") (pinfunction "2_2") (pintype "passive"))
    )
    (net (code "88") (name "Net-(IC10-~{PDN})") (class "Default")
      (node (ref "IC10") (pin "55") (pinfunction "~{PDN}_55") (pintype "input"))
      (node (ref "R34") (pin "1") (pinfunction "1_1") (pintype "passive"))
    )
    (net (code "89") (name "Net-(IC10-~{RESET})") (class "Default")
      (node (ref "IC10") (pin "54") (pinfunction "~{RESET}_54") (pintype "input"))
      (node (ref "R35") (pin "1") (pinfunction "1_1") (pintype "passive"))
    )
    (net (code "90") (name "Net-(IC11-NR)") (class "Default")
      (node (ref "C51") (pin "1") (pinfunction "1_1") (pintype "passive"))
      (node (ref "IC11") (pin "5") (pinfunction "NR_5") (pintype "passive"))
    )
    (net (code "91") (name "Net-(IC15-IN1)") (class "Default")
      (node (ref "IC15") (pin "2") (pinfunction "IN1_2") (pintype "input"))
      (node (ref "R45") (pin "2") (pinfunction "2_2") (pintype "passive"))
    )
    (net (code "92") (name "Net-(IC15-IN2)") (class "Default")
      (node (ref "IC15") (pin "3") (pinfunction "IN2_3") (pintype "input"))
      (node (ref "R46") (pin "2") (pinfunction "2_2") (pintype "passive"))
    )
    (net (code "93") (name "Net-(IC15-OUT1)") (class "Default")
      (node (ref "IC15") (pin "7") (pinfunction "OUT1_7") (pintype "output"))
      (node (ref "R54") (pin "1") (pinfunction "1_1") (pintype "passive"))
    )
    (net (code "94") (name "Net-(IC15-OUT2)") (class "Default")
      (node (ref "IC15") (pin "6") (pinfunction "OUT2_6") (pintype "output"))
      (node (ref "R55") (pin "1") (pinfunction "1_1") (pintype "passive"))
    )
    (net (code "95") (name "Net-(IC16-IN1)") (class "Default")
      (node (ref "IC16") (pin "2") (pinfunction "IN1_2") (pintype "input"))
      (node (ref "R47") (pin "2") (pinfunction "2_2") (pintype "passive"))
    )
    (net (code "96") (name "Net-(IC16-IN2)") (class "Default")
      (node (ref "IC16") (pin "3") (pinfunction "IN2_3") (pintype "input"))
      (node (ref "R48") (pin "2") (pinfunction "2_2") (pintype "passive"))
    )
    (net (code "97") (name "Net-(IC16-OUT1)") (class "Default")
      (node (ref "IC16") (pin "7") (pinfunction "OUT1_7") (pintype "output"))
      (node (ref "R56") (pin "1") (pinfunction "1_1") (pintype "passive"))
      (node (ref "R57") (pin "1") (pinfunction "1_1") (pintype "passive"))
    )
    (net (code "98") (name "Net-(IC16-OUT2)") (class "Default")
      (node (ref "IC16") (pin "6") (pinfunction "OUT2_6") (pintype "output"))
      (node (ref "R58") (pin "1") (pinfunction "1_1") (pintype "passive"))
    )
    (net (code "99") (name "Net-(IC17-IN1)") (class "Default")
      (node (ref "IC17") (pin "2") (pinfunction "IN1_2") (pintype "input"))
      (node (ref "R59") (pin "1") (pinfunction "1_1") (pintype "passive"))
    )
    (net (code "100") (name "Net-(IC17-IN2)") (class "Default")
      (node (ref "IC17") (pin "3") (pinfunction "IN2_3") (pintype "input"))
      (node (ref "R60") (pin "1") (pinfunction "1_1") (pintype "passive"))
    )
    (net (code "101") (name "Net-(IC17-OUT1)") (class "Default")
      (node (ref "IC17") (pin "7") (pinfunction "OUT1_7") (pintype "output"))
      (node (ref "R49") (pin "2") (pinfunction "2_2") (pintype "passive"))
    )
    (net (code "102") (name "Net-(IC17-OUT2)") (class "Default")
      (node (ref "IC17") (pin "6") (pinfunction "OUT2_6") (pintype "output"))
      (node (ref "R50") (pin "2") (pinfunction "2_2") (pintype "passive"))
    )
    (net (code "103") (name "Net-(IC18-IN1)") (class "Default")
      (node (ref "IC18") (pin "2") (pinfunction "IN1_2") (pintype "input"))
      (node (ref "R61") (pin "1") (pinfunction "1_1") (pintype "passive"))
    )
    (net (code "104") (name "Net-(IC18-IN2)") (class "Default")
      (node (ref "IC18") (pin "3") (pinfunction "IN2_3") (pintype "input"))
      (node (ref "R62") (pin "1") (pinfunction "1_1") (pintype "passive"))
    )
    (net (code "105") (name "Net-(IC18-OUT1)") (class "Default")
      (node (ref "IC18") (pin "7") (pinfunction "OUT1_7") (pintype "output"))
      (node (ref "R51") (pin "2") (pinfunction "2_2") (pintype "passive"))
    )
    (net (code "106") (name "Net-(IC18-OUT2)") (class "Default")
      (node (ref "IC18") (pin "6") (pinfunction "OUT2_6") (pintype "output"))
      (node (ref "R52") (pin "2") (pinfunction "2_2") (pintype "passive"))
    )
    (net (code "107") (name "Net-(JP1-Pad1)") (class "Default")
      (node (ref "JP1") (pin "1") (pinfunction "1_1") (pintype "passive"))
      (node (ref "R10") (pin "1") (pinfunction "1_1") (pintype "passive"))
      (node (ref "R8") (pin "1") (pinfunction "1_1") (pintype "passive"))
    )
    (net (code "108") (name "Net-(JP1-Pad2)") (class "Default")
      (node (ref "JP1") (pin "2") (pinfunction "2_2") (pintype "passive"))
      (node (ref "R11") (pin "1") (pinfunction "1_1") (pintype "passive"))
      (node (ref "R9") (pin "1") (pinfunction "1_1") (pintype "passive"))
    )
    (net (code "109") (name "Net-(R42-Pad2)") (class "Default")
      (node (ref "R42") (pin "2") (pinfunction "2_2") (pintype "passive"))
      (node (ref "X1") (pin "3") (pinfunction "OUT_3") (pintype "output"))
      (node (ref "X1") (pin "3-2") (pinfunction "OUT_3-2") (pintype "output"))
    )
    (net (code "110") (name "OSC_CLK") (class "Default")
      (node (ref "IC10") (pin "45") (pinfunction "XTAL2/IN_45") (pintype "input"))
      (node (ref "R42") (pin "1") (pinfunction "1_1") (pintype "passive"))
    )
    (net (code "111") (name "V+") (class "Default")
      (node (ref "C13") (pin "1") (pinfunction "1_1") (pintype "passive"))
      (node (ref "C16") (pin "1") (pinfunction "1_1") (pintype "passive"))
      (node (ref "C21") (pin "+") (pinfunction "1_+") (pintype "passive"))
      (node (ref "C25") (pin "1") (pinfunction "1_1") (pintype "passive"))
      (node (ref "FB5") (pin "2") (pinfunction "2_2") (pintype "passive"))
      (node (ref "IC5") (pin "3") (pinfunction "IN_3") (pintype "input"))
      (node (ref "IC6") (pin "3") (pinfunction "IN_3") (pintype "input"))
    )
    (net (code "112") (name "V-") (class "Default")
      (node (ref "C17") (pin "2") (pinfunction "2_2") (pintype "passive"))
      (node (ref "C22") (pin "-") (pinfunction "2_-") (pintype "passive"))
      (node (ref "C26") (pin "2") (pinfunction "2_2") (pintype "passive"))
      (node (ref "C27") (pin "2") (pinfunction "2_2") (pintype "passive"))
      (node (ref "FB6") (pin "2") (pinfunction "2_2") (pintype "passive"))
      (node (ref "IC7") (pin "2") (pinfunction "IN_2") (pintype "input"))
      (node (ref "IC8") (pin "2") (pinfunction "IN_2") (pintype "input"))
    )
    (net (code "113") (name "VCC_OSC") (class "Default")
      (node (ref "C65") (pin "1") (pinfunction "1_1") (pintype "passive"))
      (node (ref "C66") (pin "1") (pinfunction "1_1") (pintype "passive"))
      (node (ref "IC13") (pin "5") (pinfunction "OUT_5") (pintype "output"))
      (node (ref "X1") (pin "1") (pinfunction "EN_1") (pintype "input"))
      (node (ref "X1") (pin "1-2") (pinfunction "EN_1-2") (pintype "input"))
      (node (ref "X1") (pin "4") (pinfunction "VCC_4") (pintype "input"))
      (node (ref "X1") (pin "4-2") (pinfunction "VCC_4-2") (pintype "input"))
    )
    (net (code "114") (name "VIN") (class "Default")
      (node (ref "C3") (pin "1") (pinfunction "1_1") (pintype "passive"))
      (node (ref "IC1") (pin "117") (pinfunction "VIN_117") (pintype "bidirectional"))
      (node (ref "IC1") (pin "118") (pinfunction "VIN_118") (pintype "bidirectional"))
      (node (ref "IC1") (pin "119") (pinfunction "VIN_119") (pintype "bidirectional"))
      (node (ref "IC1") (pin "120") (pinfunction "VIN_120") (pintype "bidirectional"))
      (node (ref "IC2") (pin "1") (pinfunction "IN_1") (pintype "input"))
    )
    (net (code "115") (name "VREF") (class "Default")
      (node (ref "C69") (pin "1") (pinfunction "1_1") (pintype "passive"))
      (node (ref "IC10") (pin "35") (pinfunction "REFIN_35") (pintype "input"))
      (node (ref "IC11") (pin "6") (pinfunction "VOUT_6") (pintype "output"))
    )
    (net (code "116") (name "unconnected-(IC1-+1V8-Pad105)") (class "Default")
      (node (ref "IC1") (pin "105") (pinfunction "+1V8_105") (pintype "bidirectional"))
    )
    (net (code "117") (name "unconnected-(IC1-+1V8-Pad106)") (class "Default")
      (node (ref "IC1") (pin "106") (pinfunction "+1V8_106") (pintype "bidirectional"))
    )
    (net (code "118") (name "unconnected-(IC1-+1V8-Pad107)") (class "Default")
      (node (ref "IC1") (pin "107") (pinfunction "+1V8_107") (pintype "bidirectional"))
    )
    (net (code "119") (name "unconnected-(IC1-+1V8-Pad108)") (class "Default")
      (node (ref "IC1") (pin "108") (pinfunction "+1V8_108") (pintype "bidirectional"))
    )
    (net (code "120") (name "unconnected-(IC1-+2V5-Pad55)") (class "Default")
      (node (ref "IC1") (pin "55") (pinfunction "+2V5_55") (pintype "bidirectional"))
    )
    (net (code "121") (name "unconnected-(IC1-+2V5-Pad56)") (class "Default")
      (node (ref "IC1") (pin "56") (pinfunction "+2V5_56") (pintype "bidirectional"))
    )
    (net (code "122") (name "unconnected-(IC1-IO2N_14{slash}K16-Pad87)") (class "Default")
      (node (ref "IC1") (pin "87") (pinfunction "IO2N_14/K16_87") (pintype "bidirectional"))
    )
    (net (code "123") (name "unconnected-(IC1-IO2N_35{slash}B5-Pad9)") (class "Default")
      (node (ref "IC1") (pin "9") (pinfunction "IO2N_35/B5_9") (pintype "bidirectional"))
    )
    (net (code "124") (name "unconnected-(IC1-IO2P_14{slash}K15-Pad85)") (class "Default")
      (node (ref "IC1") (pin "85") (pinfunction "IO2P_14/K15_85") (pintype "bidirectional"))
    )
    (net (code "125") (name "unconnected-(IC1-IO2P_35{slash}B6-Pad7)") (class "Default")
      (node (ref "IC1") (pin "7") (pinfunction "IO2P_35/B6_7") (pintype "bidirectional"))
    )
    (net (code "126") (name "unconnected-(IC1-IO3N_35{slash}A4-Pad6)") (class "Default")
      (node (ref "IC1") (pin "6") (pinfunction "IO3N_35/A4_6") (pintype "bidirectional"))
    )
    (net (code "127") (name "unconnected-(IC1-IO3P_35{slash}A5-Pad4)") (class "Default")
      (node (ref "IC1") (pin "4") (pinfunction "IO3P_35/A5_4") (pintype "bidirectional"))
    )
    (net (code "128") (name "unconnected-(IC1-IO4N_14{slash}M14-Pad91)") (class "Default")
      (node (ref "IC1") (pin "91") (pinfunction "IO4N_14/M14_91") (pintype "bidirectional"))
    )
    (net (code "129") (name "unconnected-(IC1-IO4N_35{slash}A3-Pad11)") (class "Default")
      (node (ref "IC1") (pin "11") (pinfunction "IO4N_35/A3_11") (pintype "bidirectional"))
    )
    (net (code "130") (name "unconnected-(IC1-IO4P_14{slash}L14-Pad89)") (class "Default")
      (node (ref "IC1") (pin "89") (pinfunction "IO4P_14/L14_89") (pintype "bidirectional"))
    )
    (net (code "131") (name "unconnected-(IC1-IO4P_34{slash}N1-Pad46)") (class "Default")
      (node (ref "IC1") (pin "46") (pinfunction "IO4P_34/N1_46") (pintype "bidirectional"))
    )
    (net (code "132") (name "unconnected-(IC1-IO4P_35{slash}B4-Pad13)") (class "Default")
      (node (ref "IC1") (pin "13") (pinfunction "IO4P_35/B4_13") (pintype "bidirectional"))
    )
    (net (code "133") (name "unconnected-(IC1-IO5N_34{slash}P3-Pad43)") (class "Default")
      (node (ref "IC1") (pin "43") (pinfunction "IO5N_34/P3_43") (pintype "bidirectional"))
    )
    (net (code "134") (name "unconnected-(IC1-IO5N_35{slash}C6-Pad5)") (class "Default")
      (node (ref "IC1") (pin "5") (pinfunction "IO5N_35/C6_5") (pintype "bidirectional"))
    )
    (net (code "135") (name "unconnected-(IC1-IO5P_34{slash}P4-Pad41)") (class "Default")
      (node (ref "IC1") (pin "41") (pinfunction "IO5P_34/P4_41") (pintype "bidirectional"))
    )
    (net (code "136") (name "unconnected-(IC1-IO5P_35{slash}C7-Pad3)") (class "Default")
      (node (ref "IC1") (pin "3") (pinfunction "IO5P_35/C7_3") (pintype "bidirectional"))
    )
    (net (code "137") (name "unconnected-(IC1-IO7N_14{slash}N16-Pad95)") (class "Default")
      (node (ref "IC1") (pin "95") (pinfunction "IO7N_14/N16_95") (pintype "bidirectional"))
    )
    (net (code "138") (name "unconnected-(IC1-IO7N_35{slash}C2-Pad15)") (class "Default")
      (node (ref "IC1") (pin "15") (pinfunction "IO7N_35/C2_15") (pintype "bidirectional"))
    )
    (net (code "139") (name "unconnected-(IC1-IO7P_14{slash}M16-Pad93)") (class "Default")
      (node (ref "IC1") (pin "93") (pinfunction "IO7P_14/M16_93") (pintype "bidirectional"))
    )
    (net (code "140") (name "unconnected-(IC1-IO7P_35{slash}C3-Pad17)") (class "Default")
      (node (ref "IC1") (pin "17") (pinfunction "IO7P_35/C3_17") (pintype "bidirectional"))
    )
    (net (code "141") (name "unconnected-(IC1-IO8N_14{slash}P16-Pad99)") (class "Default")
      (node (ref "IC1") (pin "99") (pinfunction "IO8N_14/P16_99") (pintype "bidirectional"))
    )
    (net (code "142") (name "unconnected-(IC1-IO8N_15{slash}B14-Pad64)") (class "Default")
      (node (ref "IC1") (pin "64") (pinfunction "IO8N_15/B14_64") (pintype "bidirectional"))
    )
    (net (code "143") (name "unconnected-(IC1-IO8N_34{slash}T2-Pad47)") (class "Default")
      (node (ref "IC1") (pin "47") (pinfunction "IO8N_34/T2_47") (pintype "bidirectional"))
    )
    (net (code "144") (name "unconnected-(IC1-IO8N_35{slash}A2-Pad8)") (class "Default")
      (node (ref "IC1") (pin "8") (pinfunction "IO8N_35/A2_8") (pintype "bidirectional"))
    )
    (net (code "145") (name "unconnected-(IC1-IO8P_14{slash}P15-Pad97)") (class "Default")
      (node (ref "IC1") (pin "97") (pinfunction "IO8P_14/P15_97") (pintype "bidirectional"))
    )
    (net (code "146") (name "unconnected-(IC1-IO8P_15{slash}C14-Pad66)") (class "Default")
      (node (ref "IC1") (pin "66") (pinfunction "IO8P_15/C14_66") (pintype "bidirectional"))
    )
    (net (code "147") (name "unconnected-(IC1-IO8P_34{slash}R3-Pad45)") (class "Default")
      (node (ref "IC1") (pin "45") (pinfunction "IO8P_34/R3_45") (pintype "bidirectional"))
    )
    (net (code "148") (name "unconnected-(IC1-IO8P_35{slash}B2-Pad10)") (class "Default")
      (node (ref "IC1") (pin "10") (pinfunction "IO8P_35/B2_10") (pintype "bidirectional"))
    )
    (net (code "149") (name "unconnected-(IC1-IO9N_14{slash}R16-Pad96)") (class "Default")
      (node (ref "IC1") (pin "96") (pinfunction "IO9N_14/R16_96") (pintype "bidirectional"))
    )
    (net (code "150") (name "unconnected-(IC1-IO9N_15{slash}B15-Pad63)") (class "Default")
      (node (ref "IC1") (pin "63") (pinfunction "IO9N_15/B15_63") (pintype "bidirectional"))
    )
    (net (code "151") (name "unconnected-(IC1-IO9N_34{slash}T3-Pad49)") (class "Default")
      (node (ref "IC1") (pin "49") (pinfunction "IO9N_34/T3_49") (pintype "bidirectional"))
    )
    (net (code "152") (name "unconnected-(IC1-IO9N_35{slash}B1-Pad12)") (class "Default")
      (node (ref "IC1") (pin "12") (pinfunction "IO9N_35/B1_12") (pintype "bidirectional"))
    )
    (net (code "153") (name "unconnected-(IC1-IO9P_14{slash}R15-Pad94)") (class "Default")
      (node (ref "IC1") (pin "94") (pinfunction "IO9P_14/R15_94") (pintype "bidirectional"))
    )
    (net (code "154") (name "unconnected-(IC1-IO9P_15{slash}D14-Pad65)") (class "Default")
      (node (ref "IC1") (pin "65") (pinfunction "IO9P_15/D14_65") (pintype "bidirectional"))
    )
    (net (code "155") (name "unconnected-(IC1-IO9P_34{slash}T4-Pad51)") (class "Default")
      (node (ref "IC1") (pin "51") (pinfunction "IO9P_34/T4_51") (pintype "bidirectional"))
    )
    (net (code "156") (name "unconnected-(IC1-IO9P_35{slash}C1-Pad14)") (class "Default")
      (node (ref "IC1") (pin "14") (pinfunction "IO9P_35/C1_14") (pintype "bidirectional"))
    )
    (net (code "157") (name "unconnected-(IC1-IO10N_15{slash}B16-Pad67)") (class "Default")
      (node (ref "IC1") (pin "67") (pinfunction "IO10N_15/B16_67") (pintype "bidirectional"))
    )
    (net (code "158") (name "unconnected-(IC1-IO10N_35{slash}D1-Pad16)") (class "Default")
      (node (ref "IC1") (pin "16") (pinfunction "IO10N_35/D1_16") (pintype "bidirectional"))
    )
    (net (code "159") (name "unconnected-(IC1-IO10P_15{slash}C16-Pad69)") (class "Default")
      (node (ref "IC1") (pin "69") (pinfunction "IO10P_15/C16_69") (pintype "bidirectional"))
    )
    (net (code "160") (name "unconnected-(IC1-IO10P_35{slash}E2-Pad18)") (class "Default")
      (node (ref "IC1") (pin "18") (pinfunction "IO10P_35/E2_18") (pintype "bidirectional"))
    )
    (net (code "161") (name "unconnected-(IC1-IO11N_14{slash}P13-Pad100)") (class "Default")
      (node (ref "IC1") (pin "100") (pinfunction "IO11N_14/P13_100") (pintype "bidirectional"))
    )
    (net (code "162") (name "unconnected-(IC1-IO11P_14{slash}N13-Pad98)") (class "Default")
      (node (ref "IC1") (pin "98") (pinfunction "IO11P_14/N13_98") (pintype "bidirectional"))
    )
    (net (code "163") (name "unconnected-(IC1-IO12N_35{slash}C4-Pad19)") (class "Default")
      (node (ref "IC1") (pin "19") (pinfunction "IO12N_35/C4_19") (pintype "bidirectional"))
    )
    (net (code "164") (name "unconnected-(IC1-IO13N_15{slash}D14-Pad72)") (class "Default")
      (node (ref "IC1") (pin "72") (pinfunction "IO13N_15/D14_72") (pintype "bidirectional"))
    )
    (net (code "165") (name "unconnected-(IC1-IO13P_15{slash}E12-Pad74)") (class "Default")
      (node (ref "IC1") (pin "74") (pinfunction "IO13P_15/E12_74") (pintype "bidirectional"))
    )
    (net (code "166") (name "unconnected-(IC1-IO14N_35{slash}F3-Pad23)") (class "Default")
      (node (ref "IC1") (pin "23") (pinfunction "IO14N_35/F3_23") (pintype "bidirectional"))
    )
    (net (code "167") (name "unconnected-(IC1-IO14P_35{slash}F4-Pad25)") (class "Default")
      (node (ref "IC1") (pin "25") (pinfunction "IO14P_35/F4_25") (pintype "bidirectional"))
    )
    (net (code "168") (name "unconnected-(IC1-IO15N_15{slash}D15-Pad70)") (class "Default")
      (node (ref "IC1") (pin "70") (pinfunction "IO15N_15/D15_70") (pintype "bidirectional"))
    )
    (net (code "169") (name "unconnected-(IC1-IO15N_35{slash}E1-Pad20)") (class "Default")
      (node (ref "IC1") (pin "20") (pinfunction "IO15N_35/E1_20") (pintype "bidirectional"))
    )
    (net (code "170") (name "unconnected-(IC1-IO15P_15{slash}D14-Pad68)") (class "Default")
      (node (ref "IC1") (pin "68") (pinfunction "IO15P_15/D14_68") (pintype "bidirectional"))
    )
    (net (code "171") (name "unconnected-(IC1-IO15P_35{slash}F2-Pad22)") (class "Default")
      (node (ref "IC1") (pin "22") (pinfunction "IO15P_35/F2_22") (pintype "bidirectional"))
    )
    (net (code "172") (name "unconnected-(IC1-IO17N_15{slash}D16-Pad71)") (class "Default")
      (node (ref "IC1") (pin "71") (pinfunction "IO17N_15/D16_71") (pintype "bidirectional"))
    )
    (net (code "173") (name "unconnected-(IC1-IO17N_35\\G1-Pad24)") (class "Default")
      (node (ref "IC1") (pin "24") (pinfunction "IO17N_35\\G1_24") (pintype "bidirectional"))
    )
    (net (code "174") (name "unconnected-(IC1-IO17P_15{slash}E16-Pad73)") (class "Default")
      (node (ref "IC1") (pin "73") (pinfunction "IO17P_15/E16_73") (pintype "bidirectional"))
    )
    (net (code "175") (name "unconnected-(IC1-IO17P_35{slash}G2-Pad26)") (class "Default")
      (node (ref "IC1") (pin "26") (pinfunction "IO17P_35/G2_26") (pintype "bidirectional"))
    )
    (net (code "176") (name "unconnected-(IC1-IO19N_35{slash}J4-Pad35)") (class "Default")
      (node (ref "IC1") (pin "35") (pinfunction "IO19N_35/J4_35") (pintype "bidirectional"))
    )
    (net (code "177") (name "unconnected-(IC1-IO19P_35{slash}J5-Pad37)") (class "Default")
      (node (ref "IC1") (pin "37") (pinfunction "IO19P_35/J5_37") (pintype "bidirectional"))
    )
    (net (code "178") (name "unconnected-(IC1-IO20N_35{slash}H1-Pad28)") (class "Default")
      (node (ref "IC1") (pin "28") (pinfunction "IO20N_35/H1_28") (pintype "bidirectional"))
    )
    (net (code "179") (name "unconnected-(IC1-IO20P_35{slash}H2-Pad30)") (class "Default")
      (node (ref "IC1") (pin "30") (pinfunction "IO20P_35/H2_30") (pintype "bidirectional"))
    )
    (net (code "180") (name "unconnected-(IC1-IO21N_15{slash}E13-Pad76)") (class "Default")
      (node (ref "IC1") (pin "76") (pinfunction "IO21N_15/E13_76") (pintype "bidirectional"))
    )
    (net (code "181") (name "unconnected-(IC1-IO21N_35{slash}H3-Pad27)") (class "Default")
      (node (ref "IC1") (pin "27") (pinfunction "IO21N_35/H3_27") (pintype "bidirectional"))
    )
    (net (code "182") (name "unconnected-(IC1-IO21P_15{slash}G14-Pad78)") (class "Default")
      (node (ref "IC1") (pin "78") (pinfunction "IO21P_15/G14_78") (pintype "bidirectional"))
    )
    (net (code "183") (name "unconnected-(IC1-IO21P_35{slash}J3-Pad29)") (class "Default")
      (node (ref "IC1") (pin "29") (pinfunction "IO21P_35/J3_29") (pintype "bidirectional"))
    )
    (net (code "184") (name "unconnected-(IC1-IO22N_15{slash}G16-Pad75)") (class "Default")
      (node (ref "IC1") (pin "75") (pinfunction "IO22N_15/G16_75") (pintype "bidirectional"))
    )
    (net (code "185") (name "unconnected-(IC1-IO22N_35{slash}J1-Pad32)") (class "Default")
      (node (ref "IC1") (pin "32") (pinfunction "IO22N_35/J1_32") (pintype "bidirectional"))
    )
    (net (code "186") (name "unconnected-(IC1-IO22P_15{slash}H16-Pad77)") (class "Default")
      (node (ref "IC1") (pin "77") (pinfunction "IO22P_15/H16_77") (pintype "bidirectional"))
    )
    (net (code "187") (name "unconnected-(IC1-IO23N_15{slash}J16-Pad81)") (class "Default")
      (node (ref "IC1") (pin "81") (pinfunction "IO23N_15/J16_81") (pintype "bidirectional"))
    )
    (net (code "188") (name "unconnected-(IC1-IO23P_15{slash}J15-Pad79)") (class "Default")
      (node (ref "IC1") (pin "79") (pinfunction "IO23P_15/J15_79") (pintype "bidirectional"))
    )
    (net (code "189") (name "unconnected-(IC1-IO24N_15{slash}G15-Pad80)") (class "Default")
      (node (ref "IC1") (pin "80") (pinfunction "IO24N_15/G15_80") (pintype "bidirectional"))
    )
    (net (code "190") (name "unconnected-(IC1-IO24N_35{slash}K2-Pad31)") (class "Default")
      (node (ref "IC1") (pin "31") (pinfunction "IO24N_35/K2_31") (pintype "bidirectional"))
    )
    (net (code "191") (name "unconnected-(IC1-IO24P_15{slash}H14-Pad82)") (class "Default")
      (node (ref "IC1") (pin "82") (pinfunction "IO24P_15/H14_82") (pintype "bidirectional"))
    )
    (net (code "192") (name "unconnected-(IC1-IO24P_35{slash}K3-Pad33)") (class "Default")
      (node (ref "IC1") (pin "33") (pinfunction "IO24P_35/K3_33") (pintype "bidirectional"))
    )
    (net (code "193") (name "unconnected-(IC2-~{FAULT}-Pad4)") (class "Default")
      (node (ref "IC2") (pin "4") (pinfunction "~{FAULT}_4") (pintype "bidirectional"))
    )
    (net (code "194") (name "unconnected-(IC10-DCLKRATE0{slash}GPIO0-Pad51)") (class "Default")
      (node (ref "IC10") (pin "51") (pinfunction "DCLKRATE0/GPIO0_51") (pintype "bidirectional"))
    )
    (net (code "195") (name "unconnected-(IC10-DCLKRATE1{slash}GPIO1-Pad52)") (class "Default")
      (node (ref "IC10") (pin "52") (pinfunction "DCLKRATE1/GPIO1_52") (pintype "bidirectional"))
    )
    (net (code "196") (name "unconnected-(IC10-DCLKRATE2{slash}GPIO2-Pad53)") (class "Default")
      (node (ref "IC10") (pin "53") (pinfunction "DCLKRATE2/GPIO2_53") (pintype "bidirectional"))
    )
    (net (code "197") (name "unconnected-(IC10-DOUT1-Pad9)") (class "Default")
      (node (ref "IC10") (pin "9") (pinfunction "DOUT1_9") (pintype "output"))
    )
    (net (code "198") (name "unconnected-(IC10-DOUT2-Pad8)") (class "Default")
      (node (ref "IC10") (pin "8") (pinfunction "DOUT2_8") (pintype "output"))
    )
    (net (code "199") (name "unconnected-(IC10-DOUT3-Pad7)") (class "Default")
      (node (ref "IC10") (pin "7") (pinfunction "DOUT3_7") (pintype "output"))
    )
    (net (code "200") (name "unconnected-(IC10-FILTER0{slash}GPIO4-Pad15)") (class "Default")
      (node (ref "IC10") (pin "15") (pinfunction "FILTER0/GPIO4_15") (pintype "bidirectional"))
    )
    (net (code "201") (name "unconnected-(IC10-FILTER1{slash}GPIO5-Pad16)") (class "Default")
      (node (ref "IC10") (pin "16") (pinfunction "FILTER1/GPIO5_16") (pintype "bidirectional"))
    )
    (net (code "202") (name "unconnected-(IC10-FRAME0{slash}GPIO6-Pad17)") (class "Default")
      (node (ref "IC10") (pin "17") (pinfunction "FRAME0/GPIO6_17") (pintype "bidirectional"))
    )
    (net (code "203") (name "unconnected-(IC10-FRAME1{slash}GPIO7-Pad18)") (class "Default")
      (node (ref "IC10") (pin "18") (pinfunction "FRAME1/GPIO7_18") (pintype "bidirectional"))
    )
    (net (code "204") (name "unconnected-(IC10-PWRMODE{slash}GPIO3-Pad56)") (class "Default")
      (node (ref "IC10") (pin "56") (pinfunction "PWRMODE/GPIO3_56") (pintype "bidirectional"))
    )
    (net (code "205") (name "unconnected-(IC10-XCLKOUT-Pad48)") (class "Default")
      (node (ref "IC10") (pin "48") (pinfunction "XCLKOUT_48") (pintype "output"))
    )
    (net (code "206") (name "unconnected-(IC10-XTAL1-Pad46)") (class "Default")
      (node (ref "IC10") (pin "46") (pinfunction "XTAL1_46") (pintype "bidirectional"))
    )
    (net (code "207") (name "unconnected-(IC11-TEMP-Pad3)") (class "Default")
      (node (ref "IC11") (pin "3") (pinfunction "TEMP_3") (pintype "output"))
    )
    (net (code "208") (name "unconnected-(SW1-PadB1)") (class "Default")
      (node (ref "SW1") (pin "B1") (pinfunction "B1_B1") (pintype "passive"))
    )
    (net (code "209") (name "unconnected-(SW1-PadB2)") (class "Default")
      (node (ref "SW1") (pin "B2") (pinfunction "B2_B2") (pintype "passive"))
    )
  )
)
